# FindMeSAT_MB_1V1.net
KiCad netlist of a schematic drawn in EAGLE
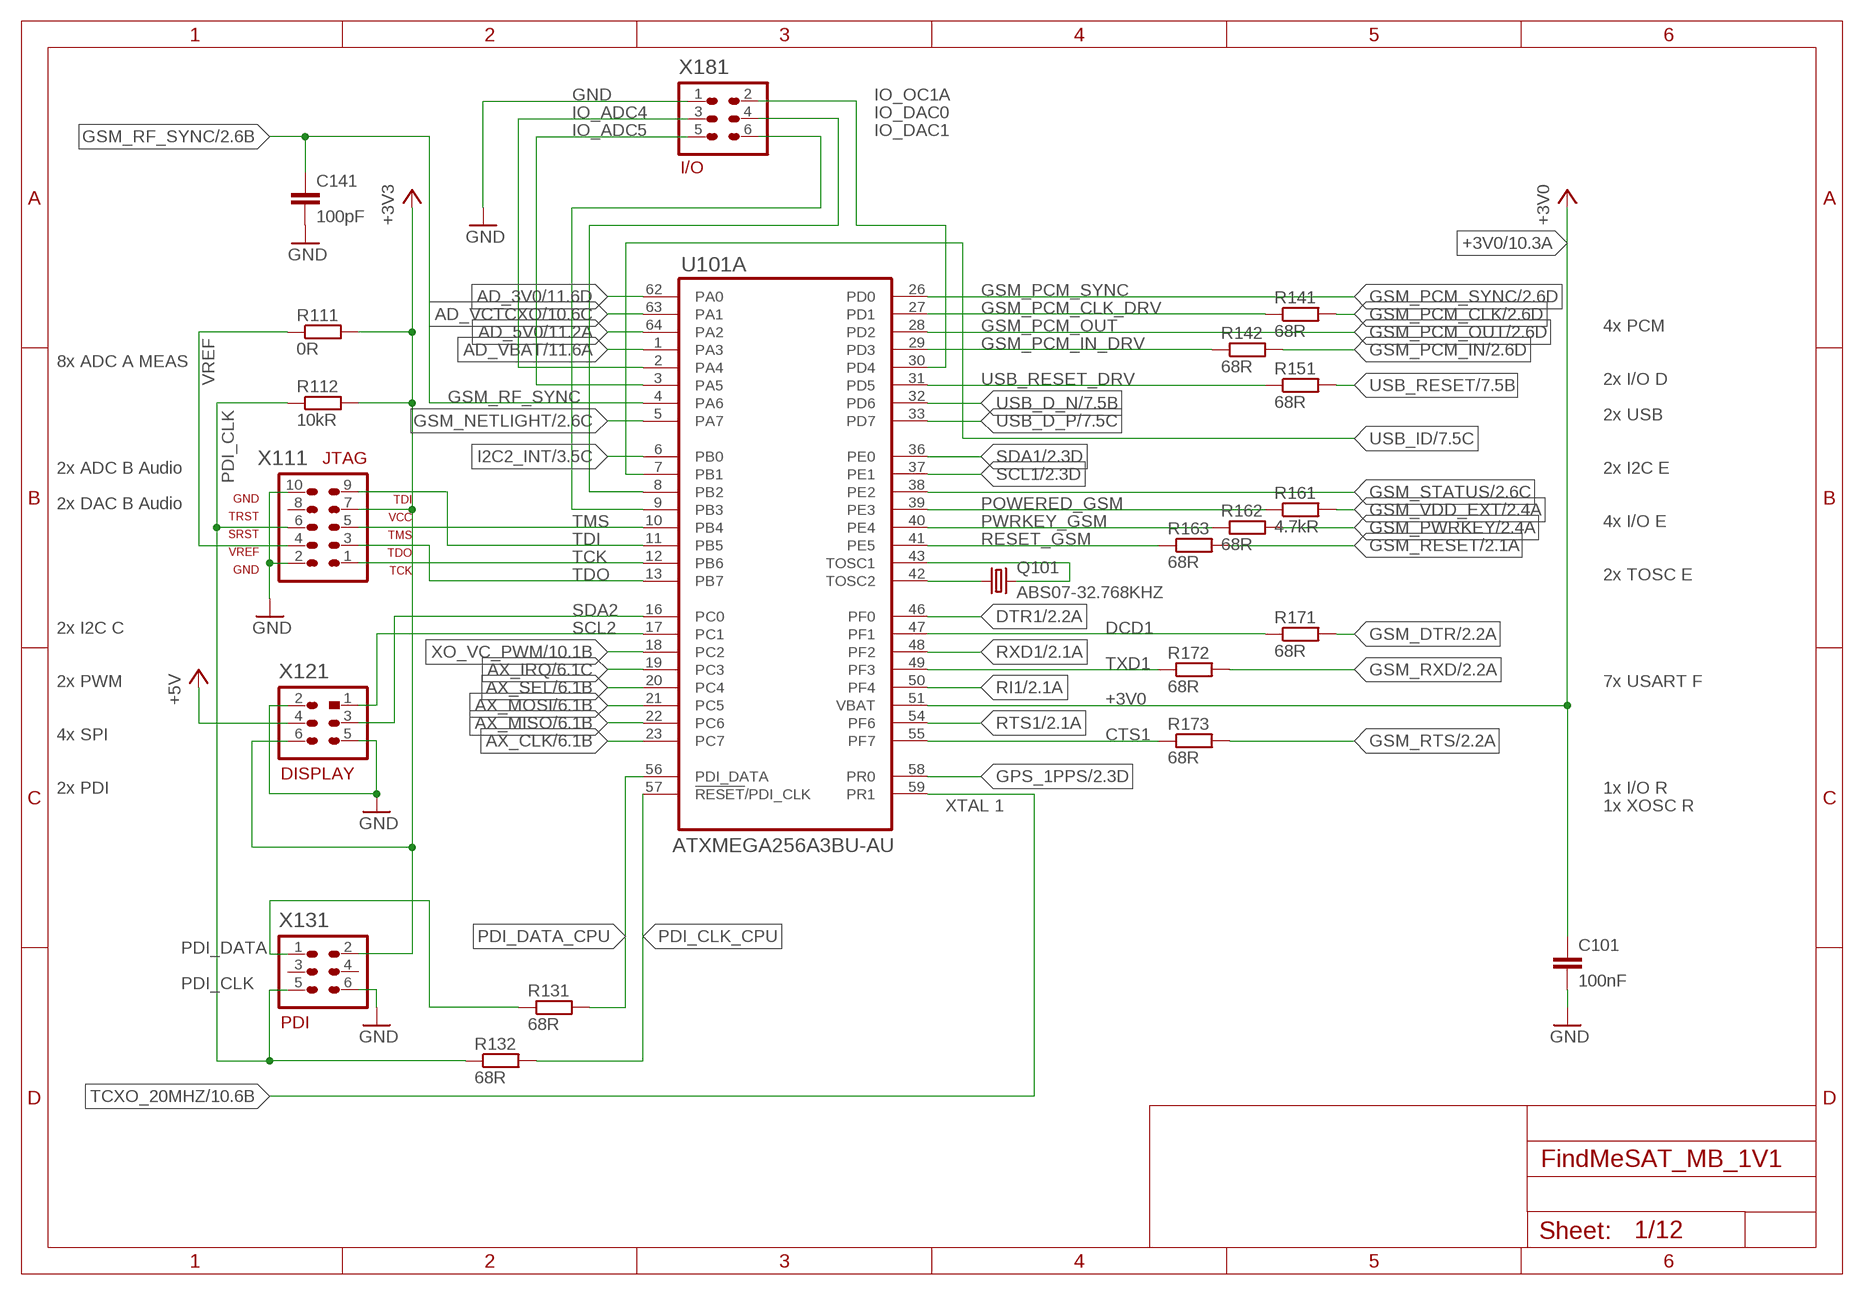
[diagram p0: schematic, sheet 1]
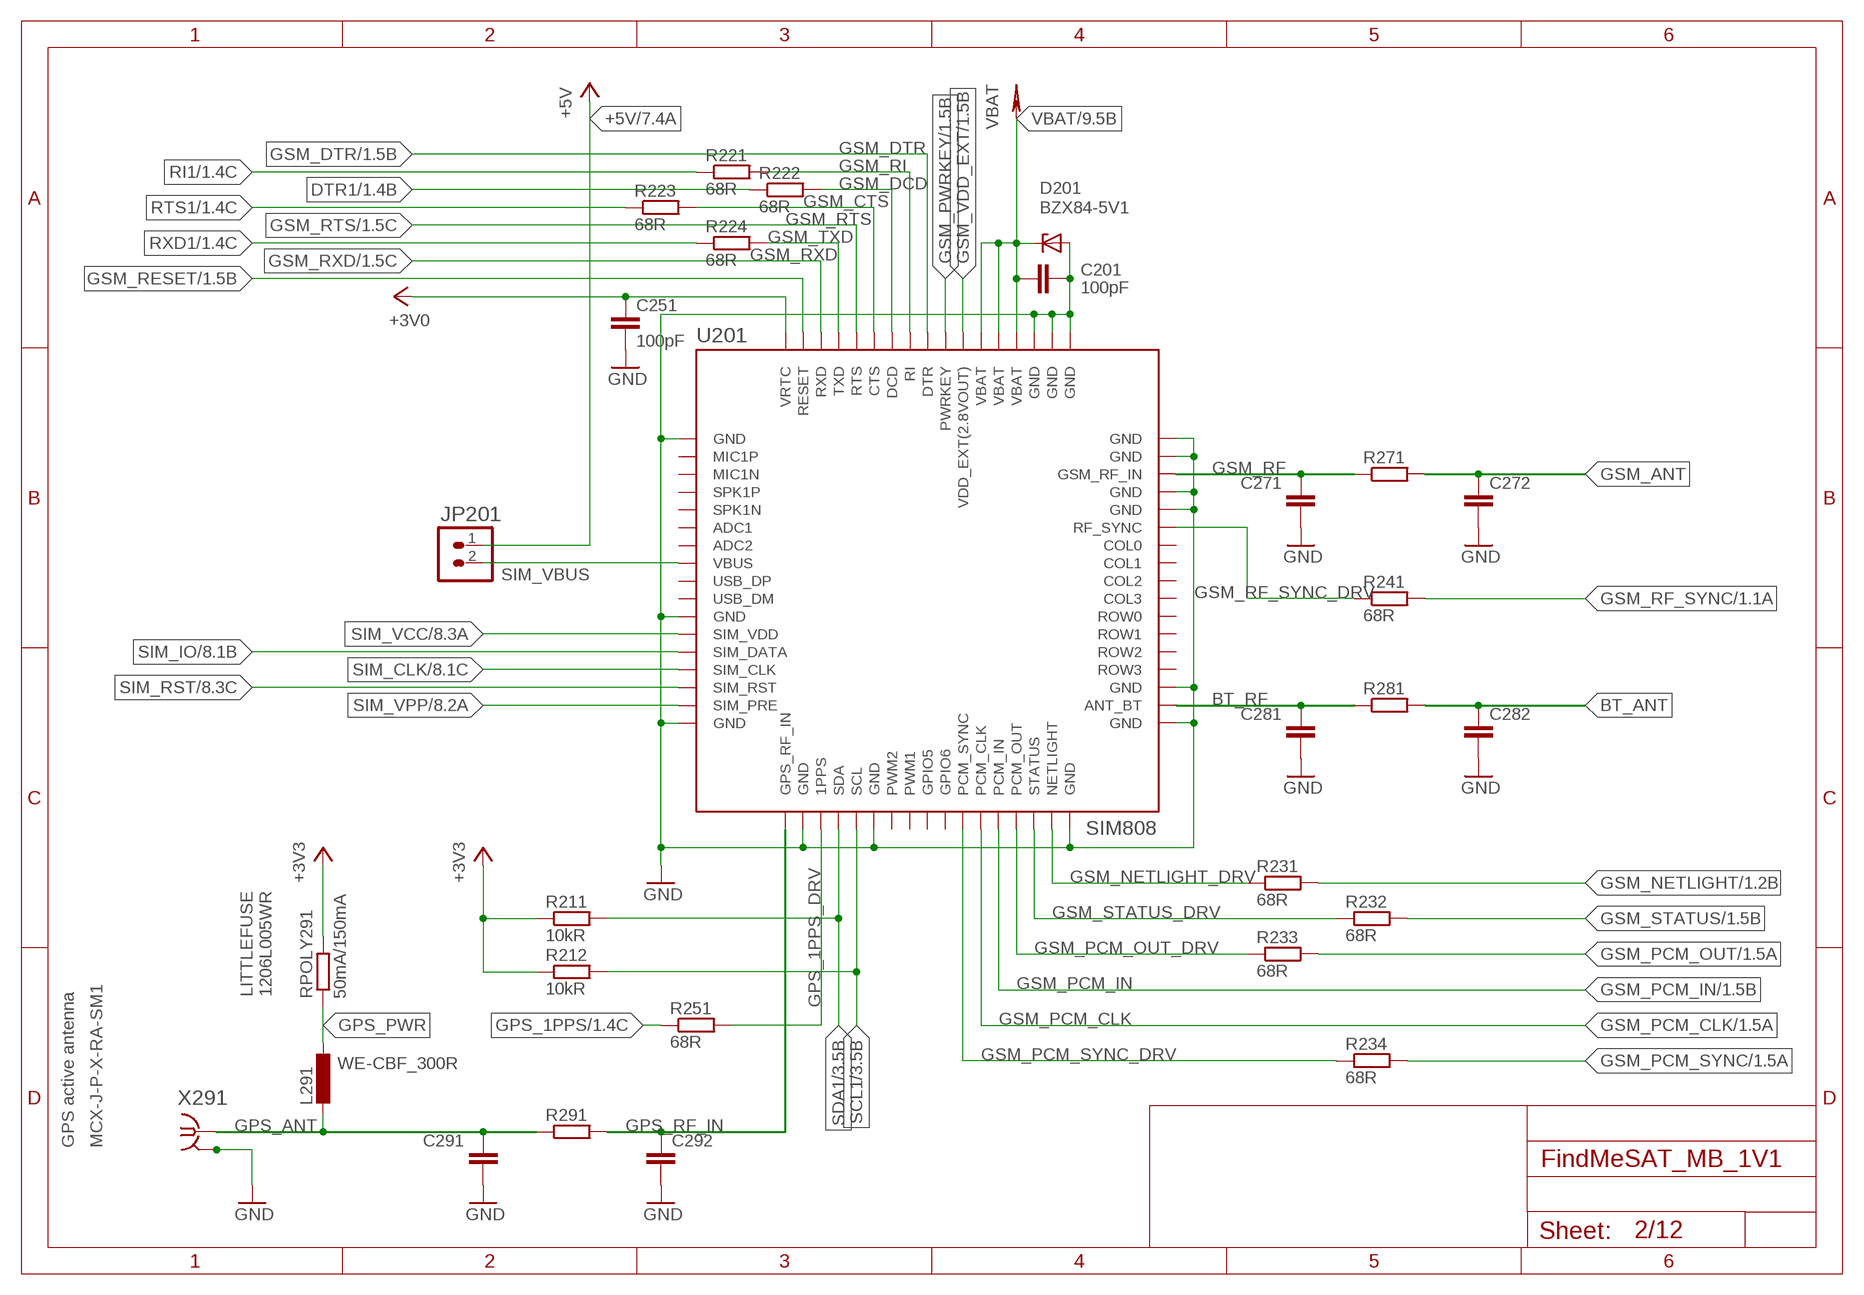
[diagram p1: schematic, sheet 2]
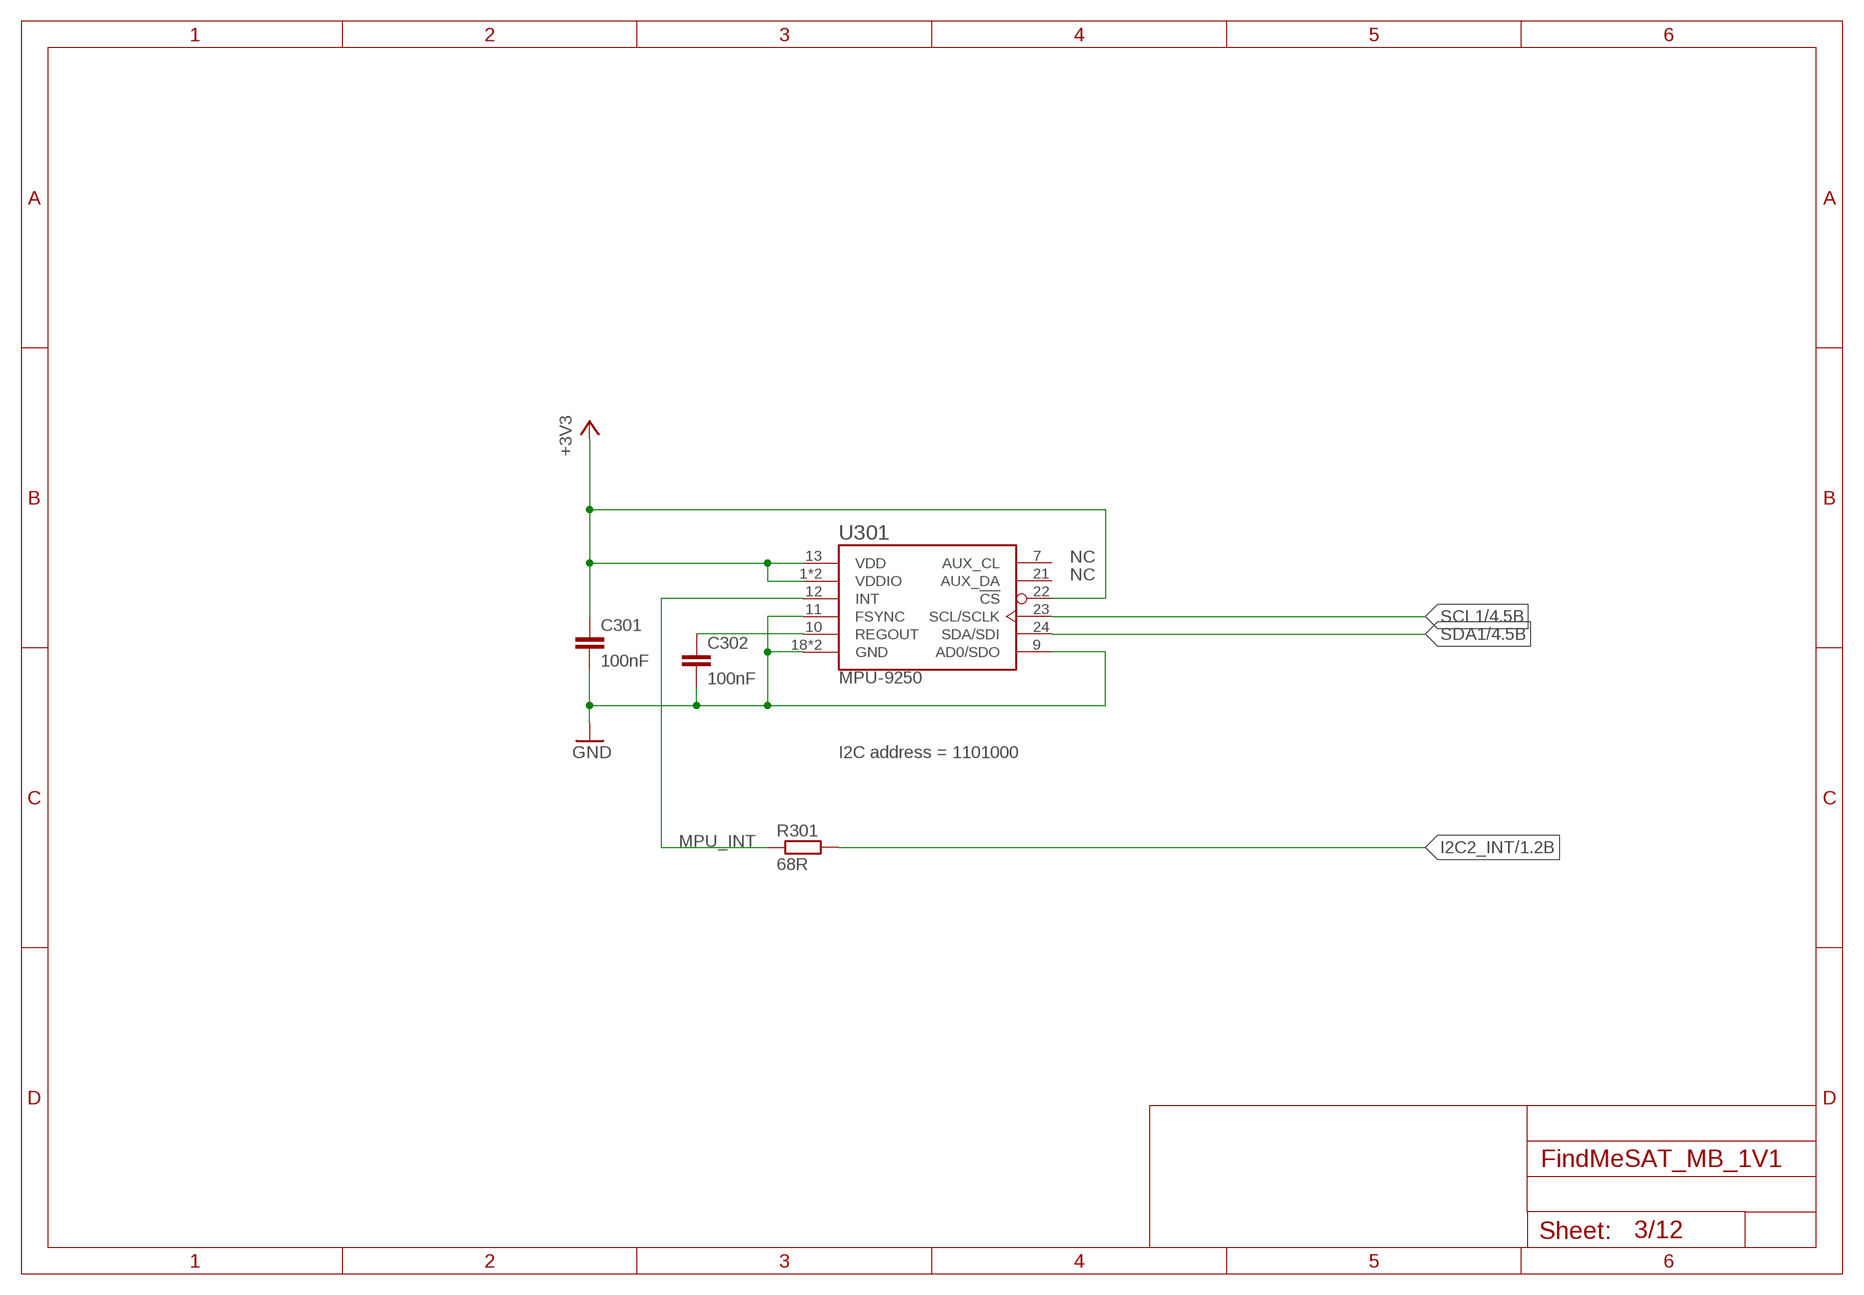
[diagram p2: schematic, sheet 3]
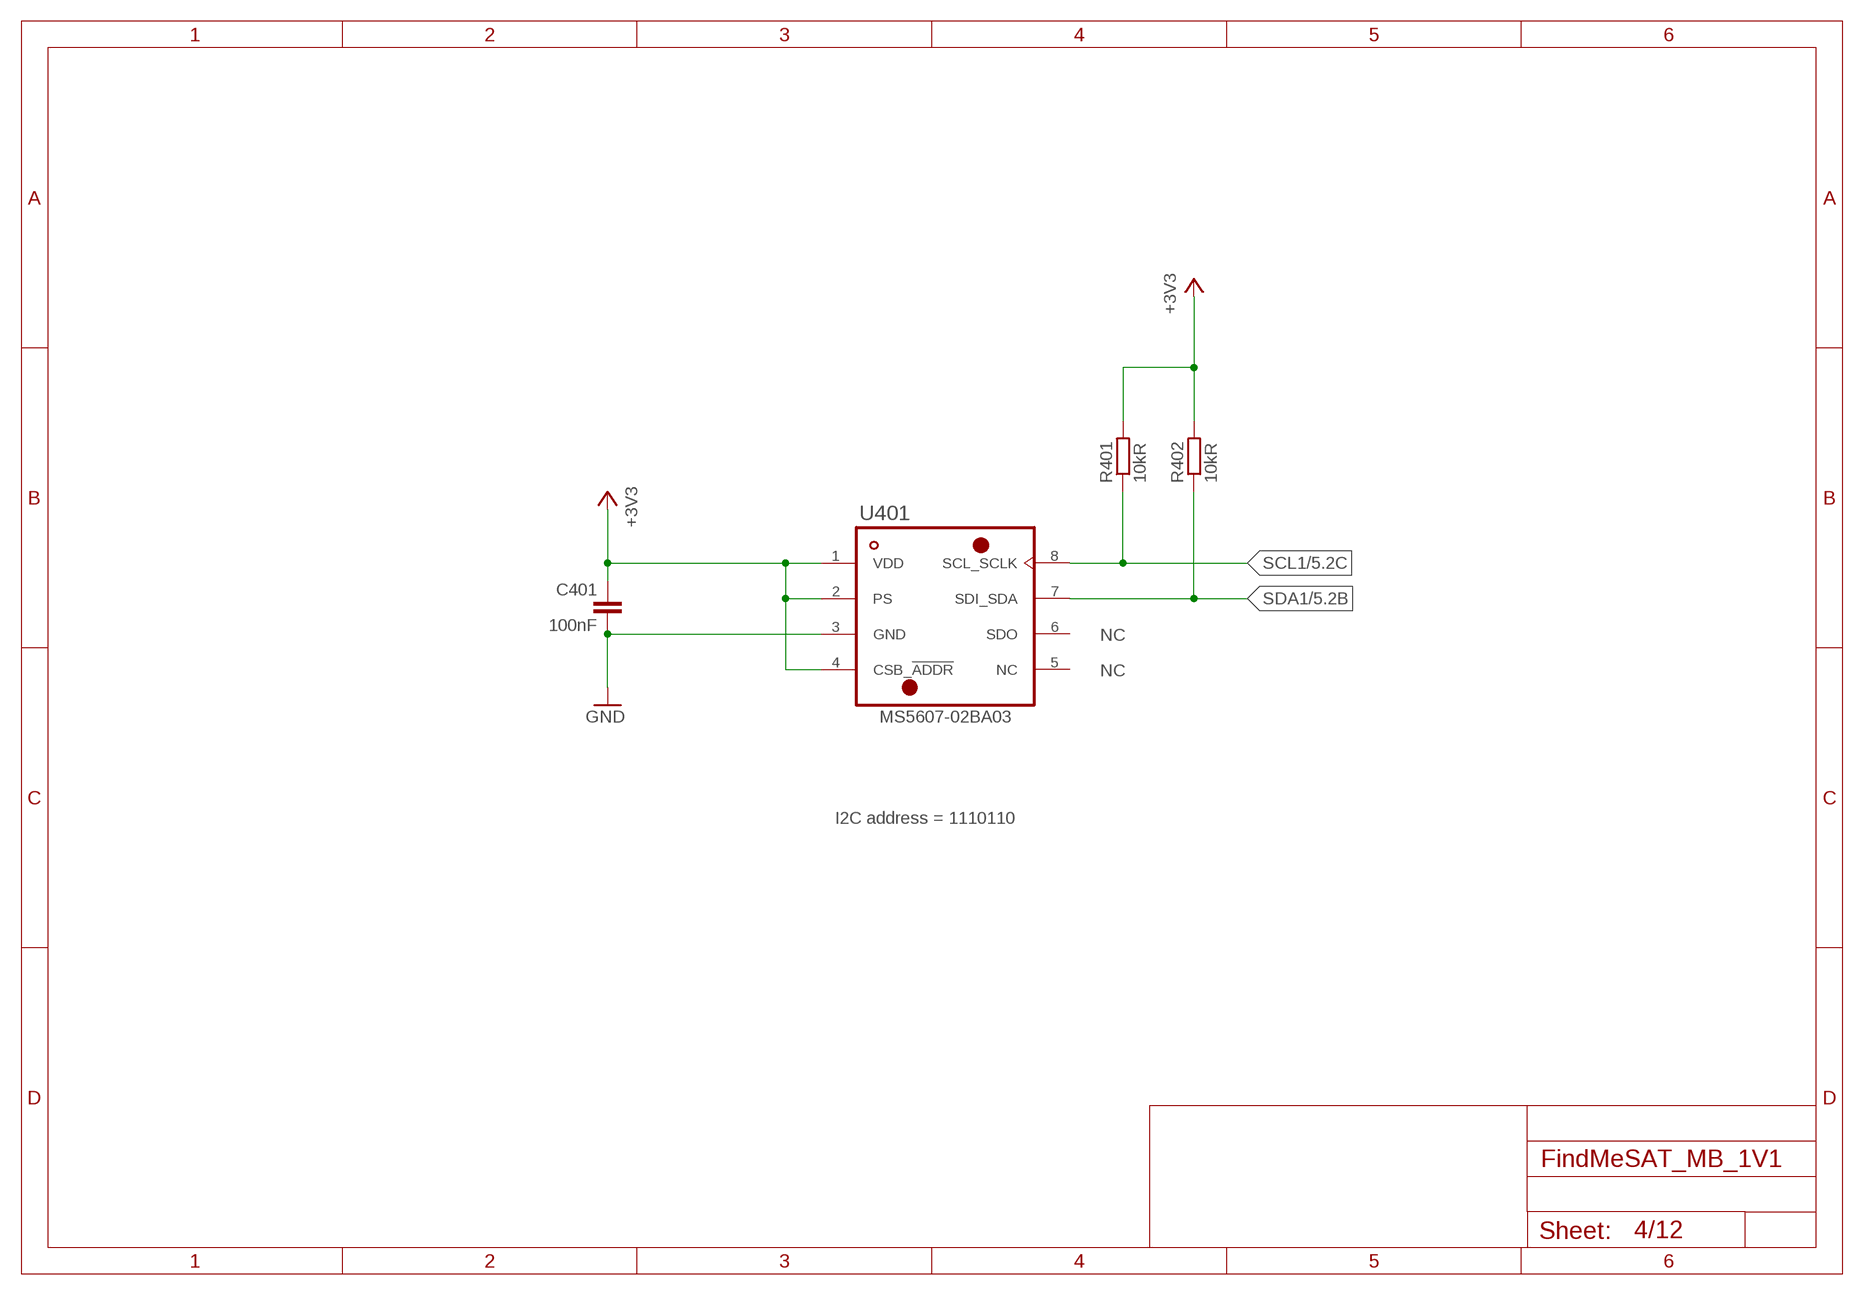
[diagram p3: schematic, sheet 4]
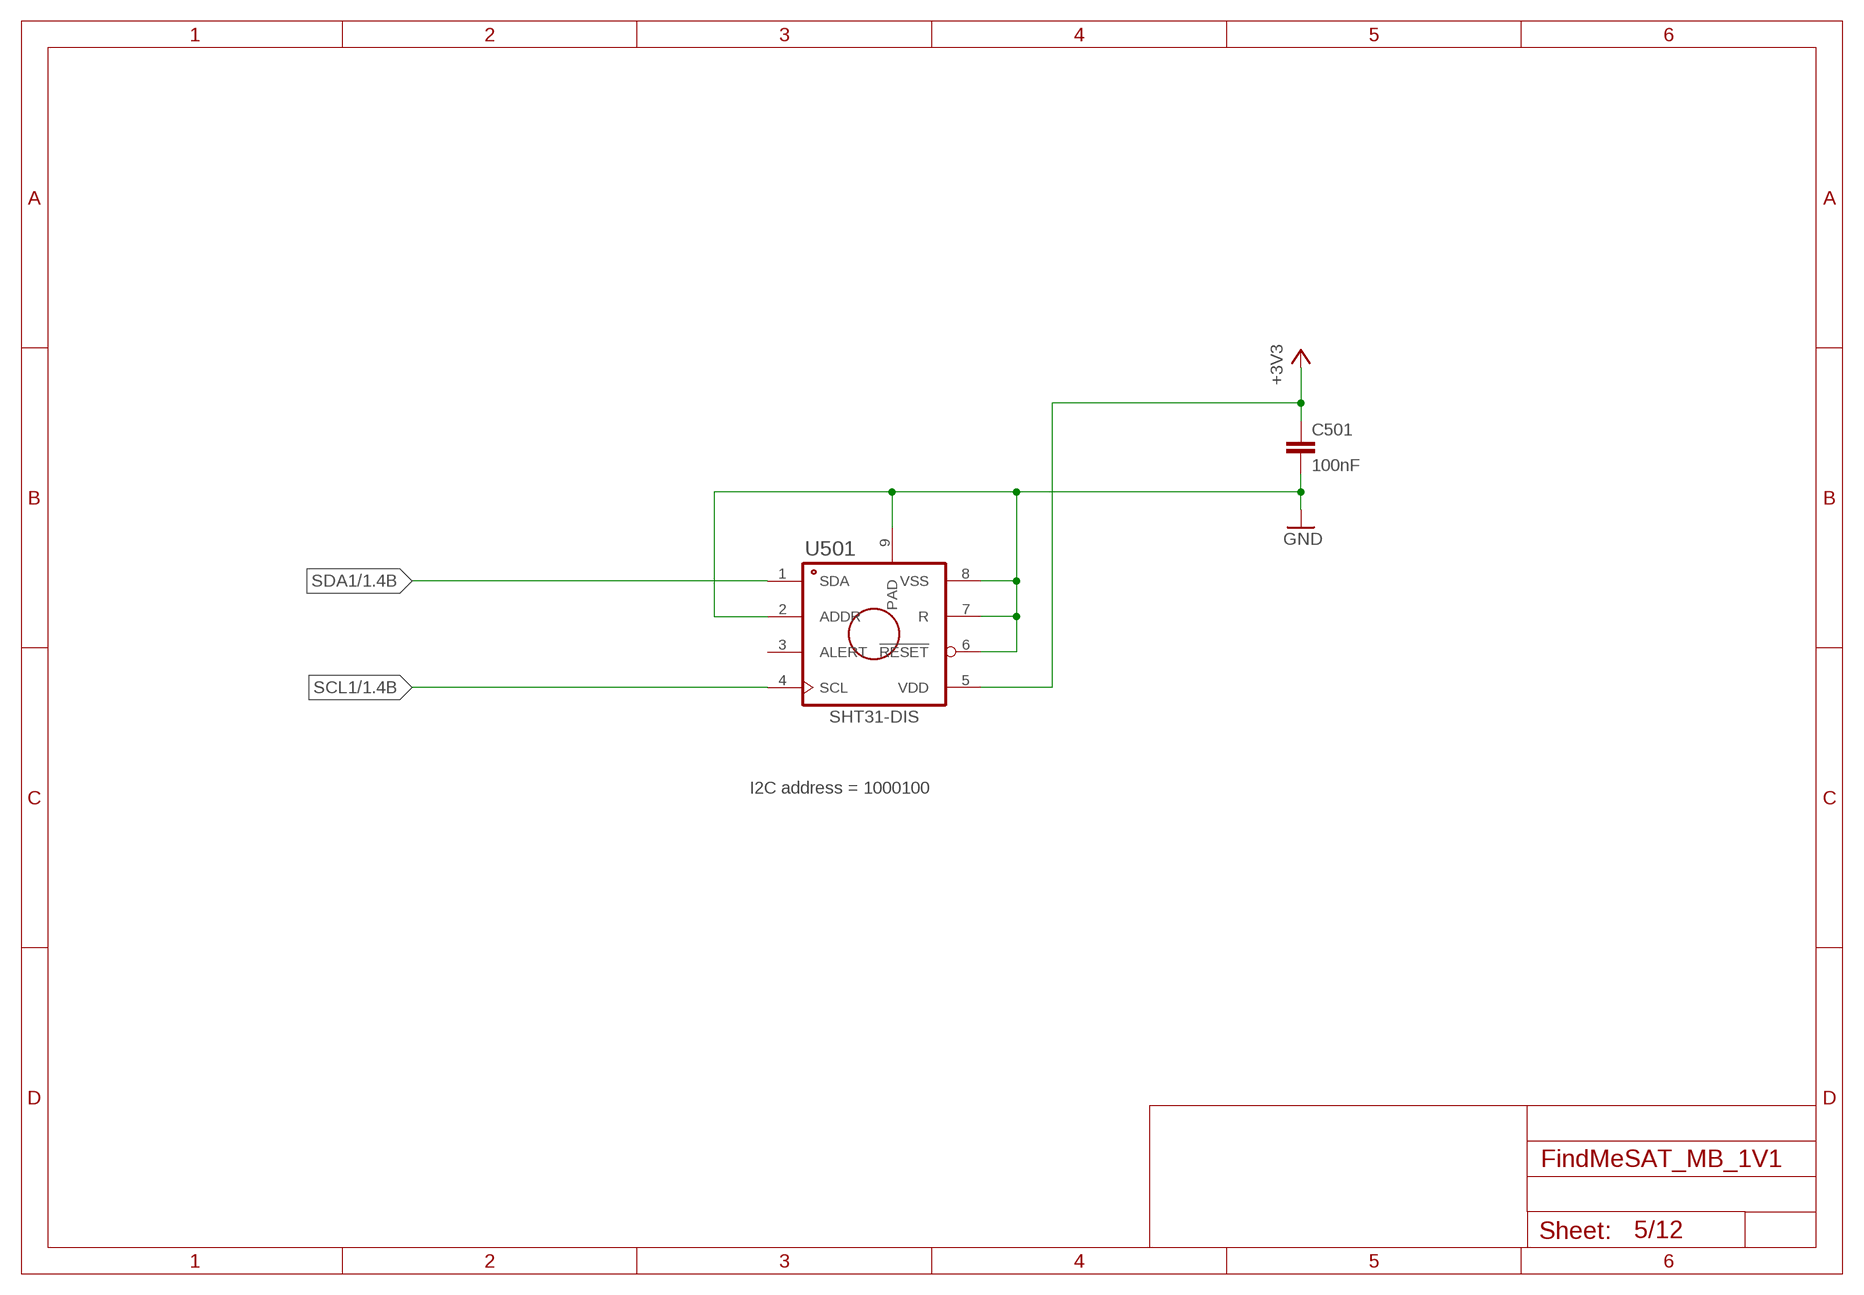
[diagram p4: schematic, sheet 5]
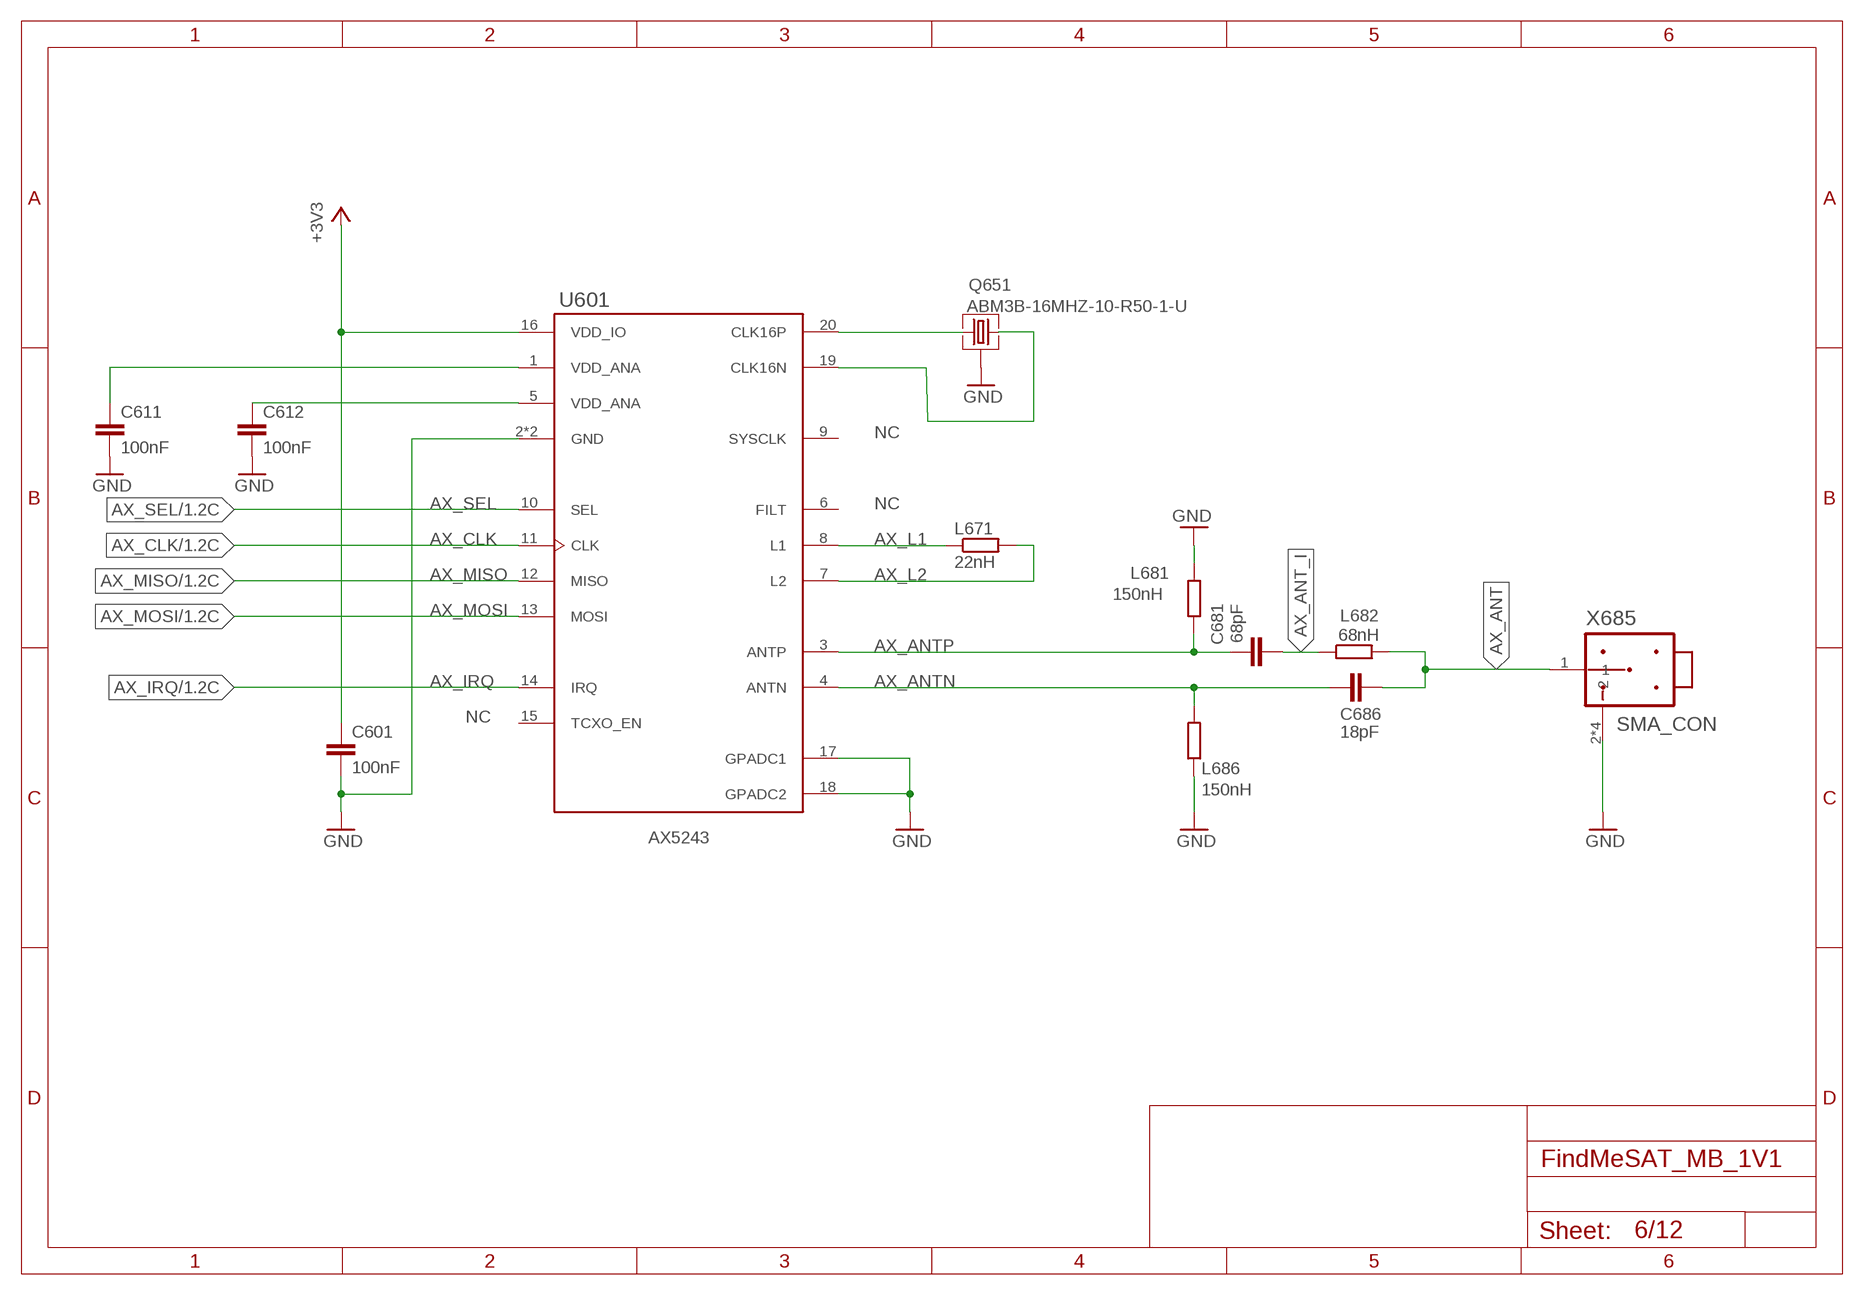
[diagram p5: schematic, sheet 6]
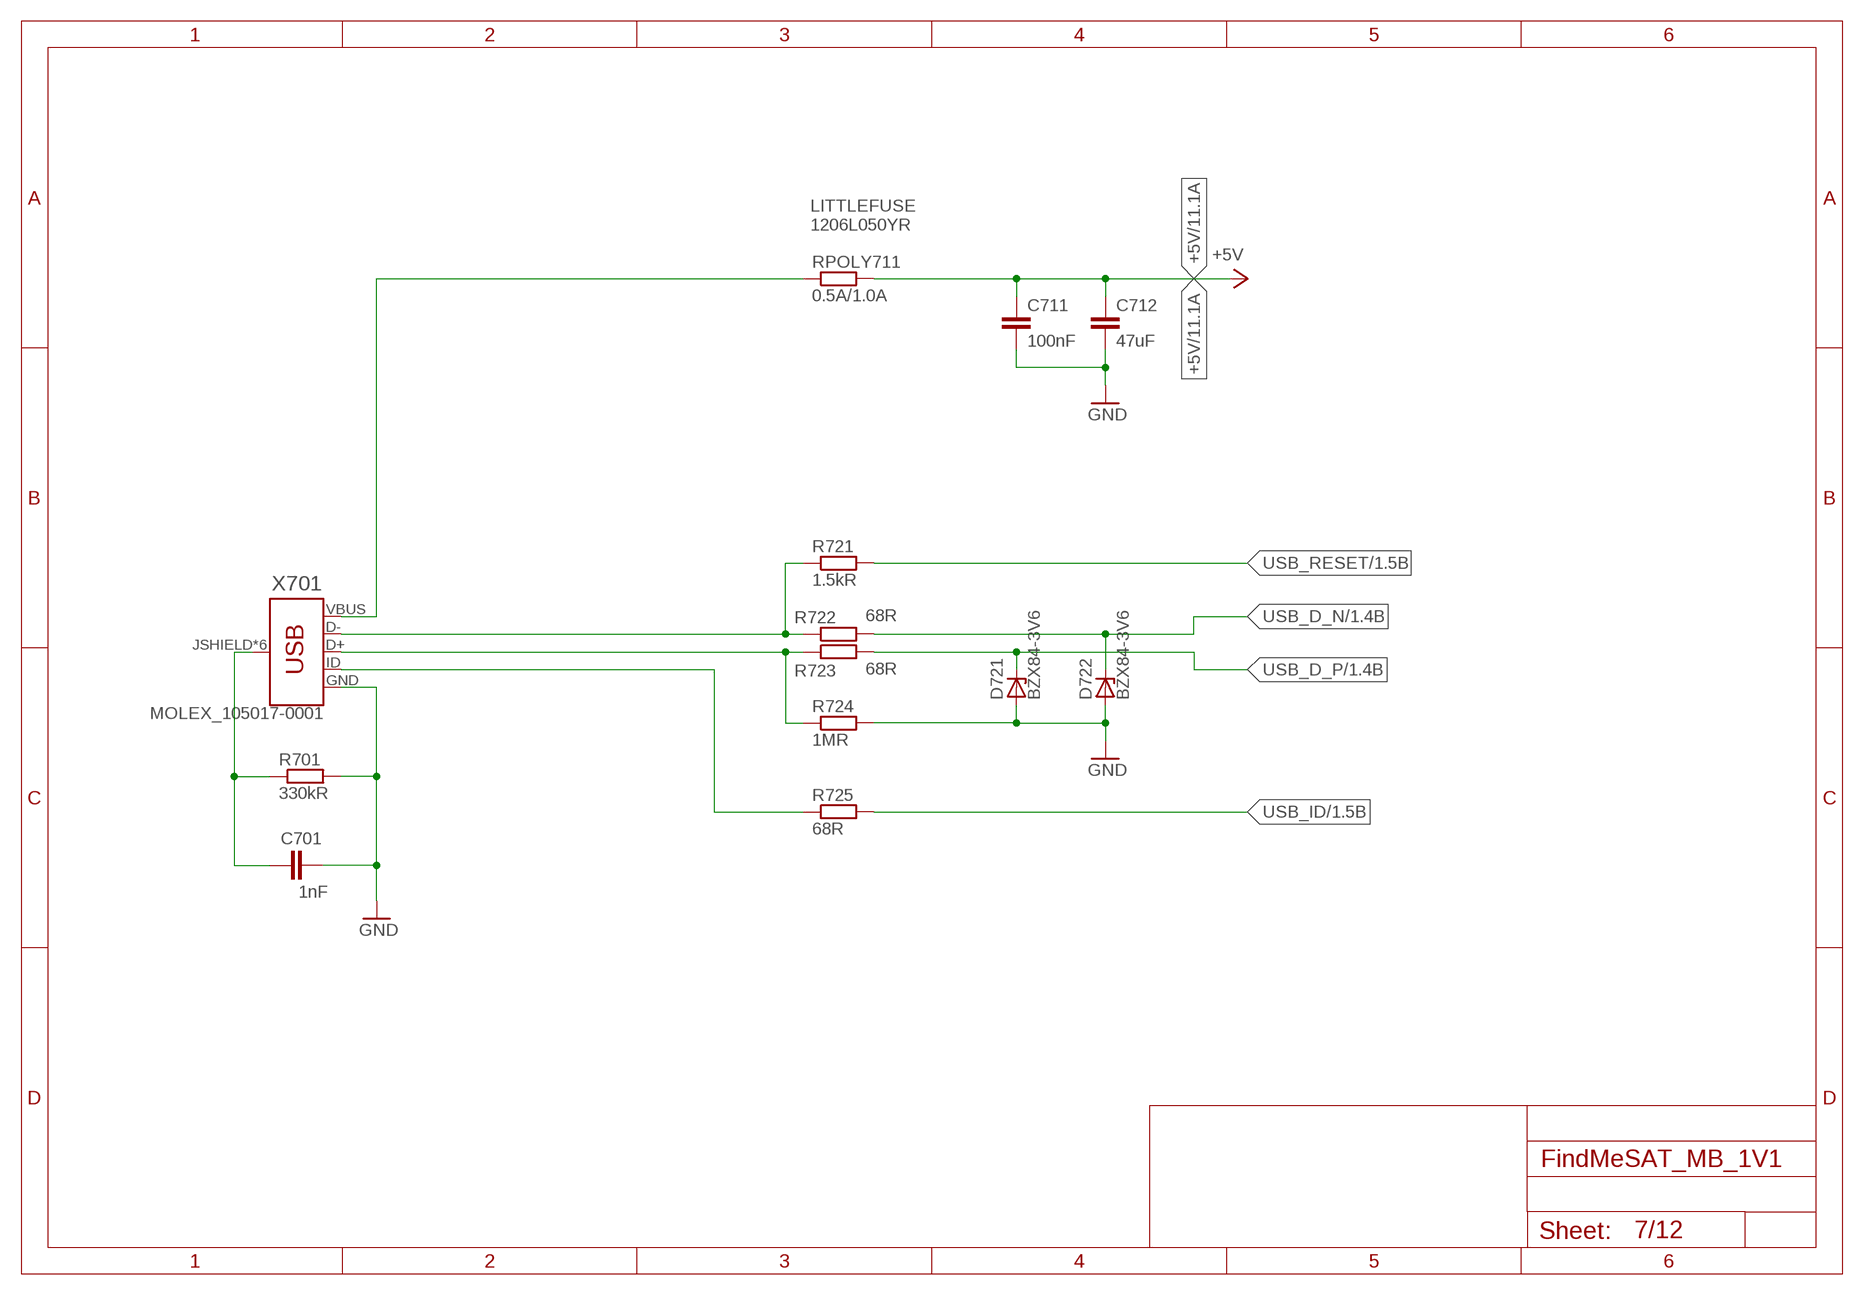
[diagram p6: schematic, sheet 7]
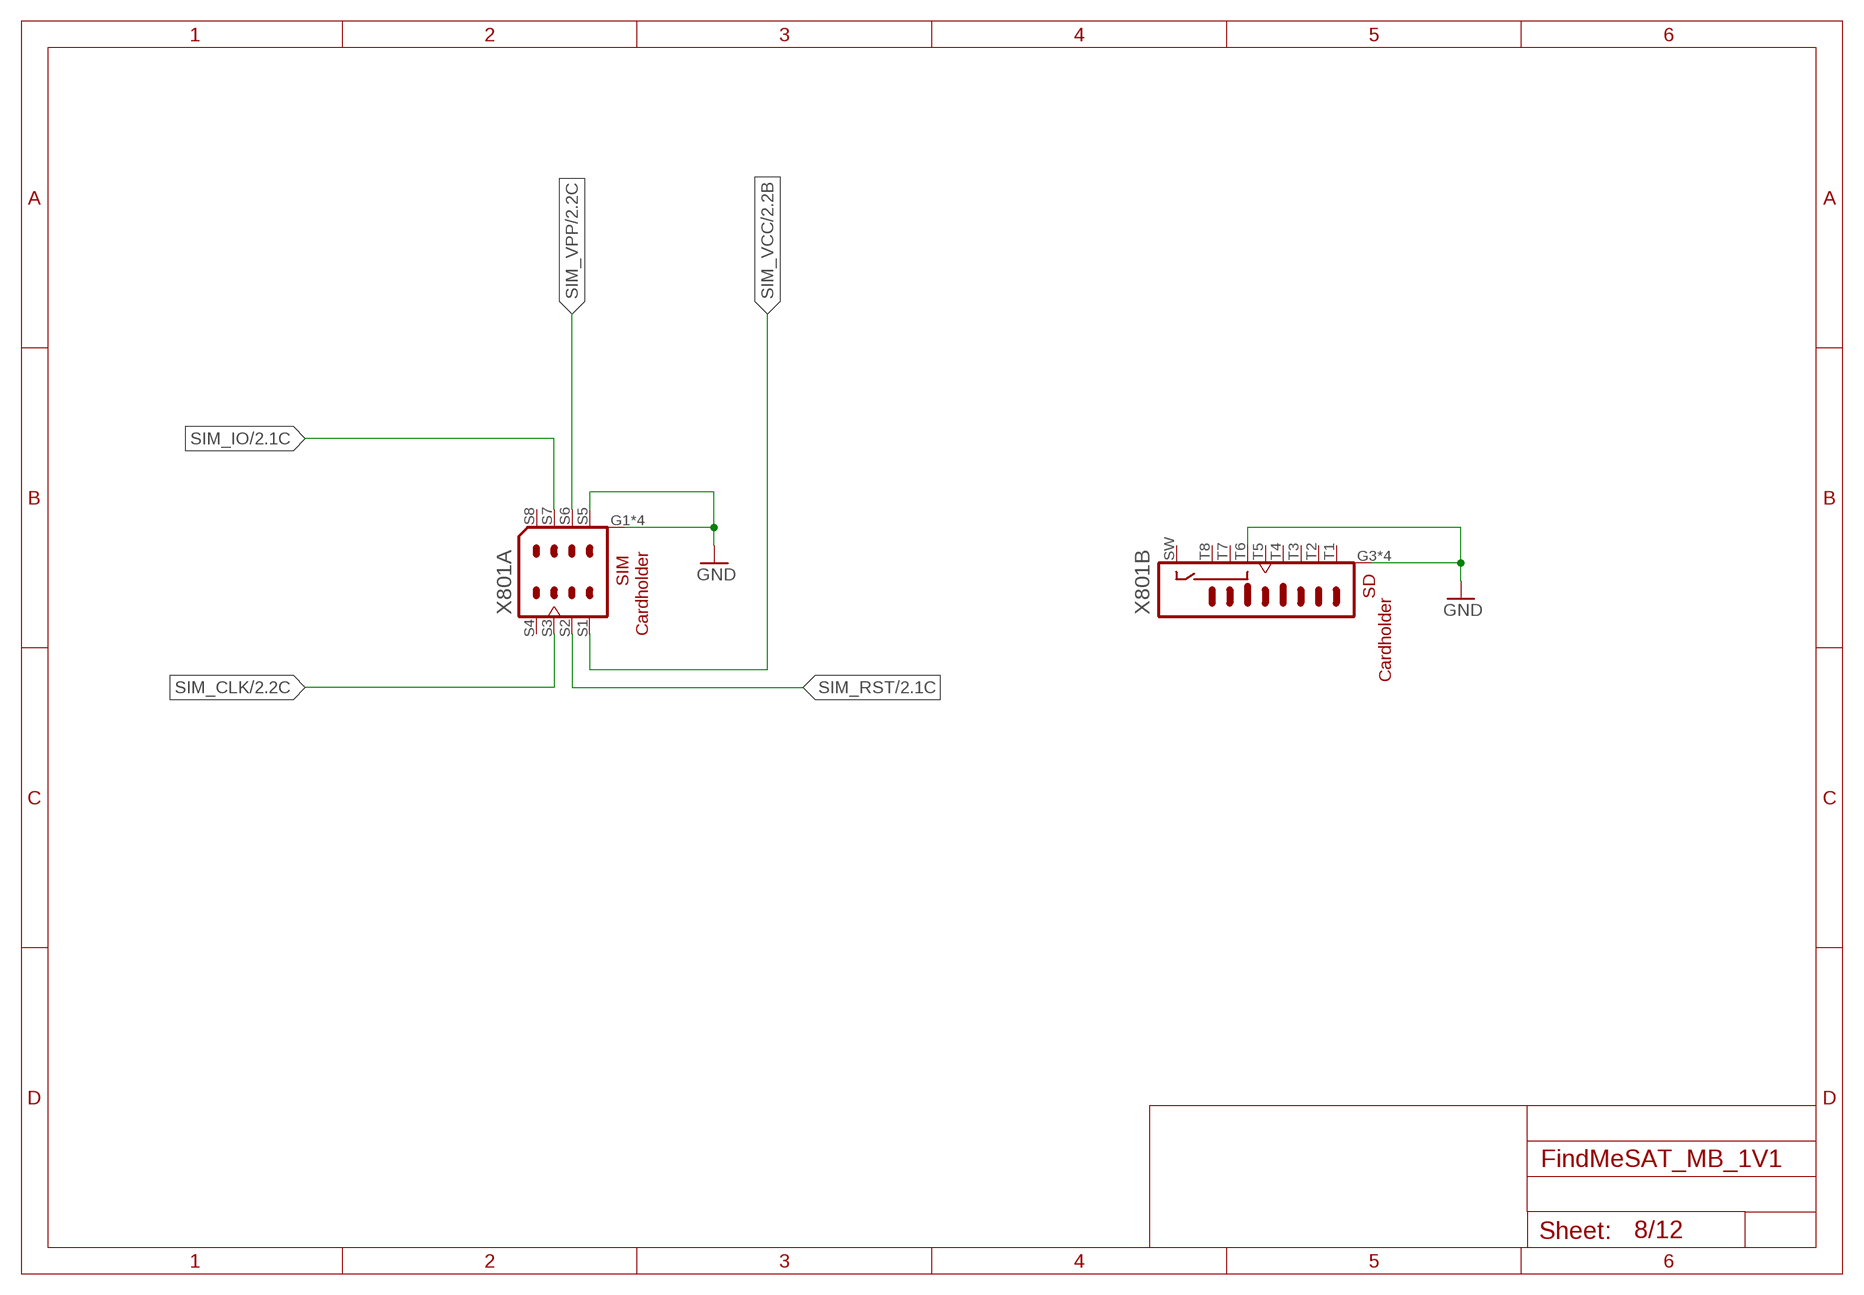
[diagram p7: schematic, sheet 8]
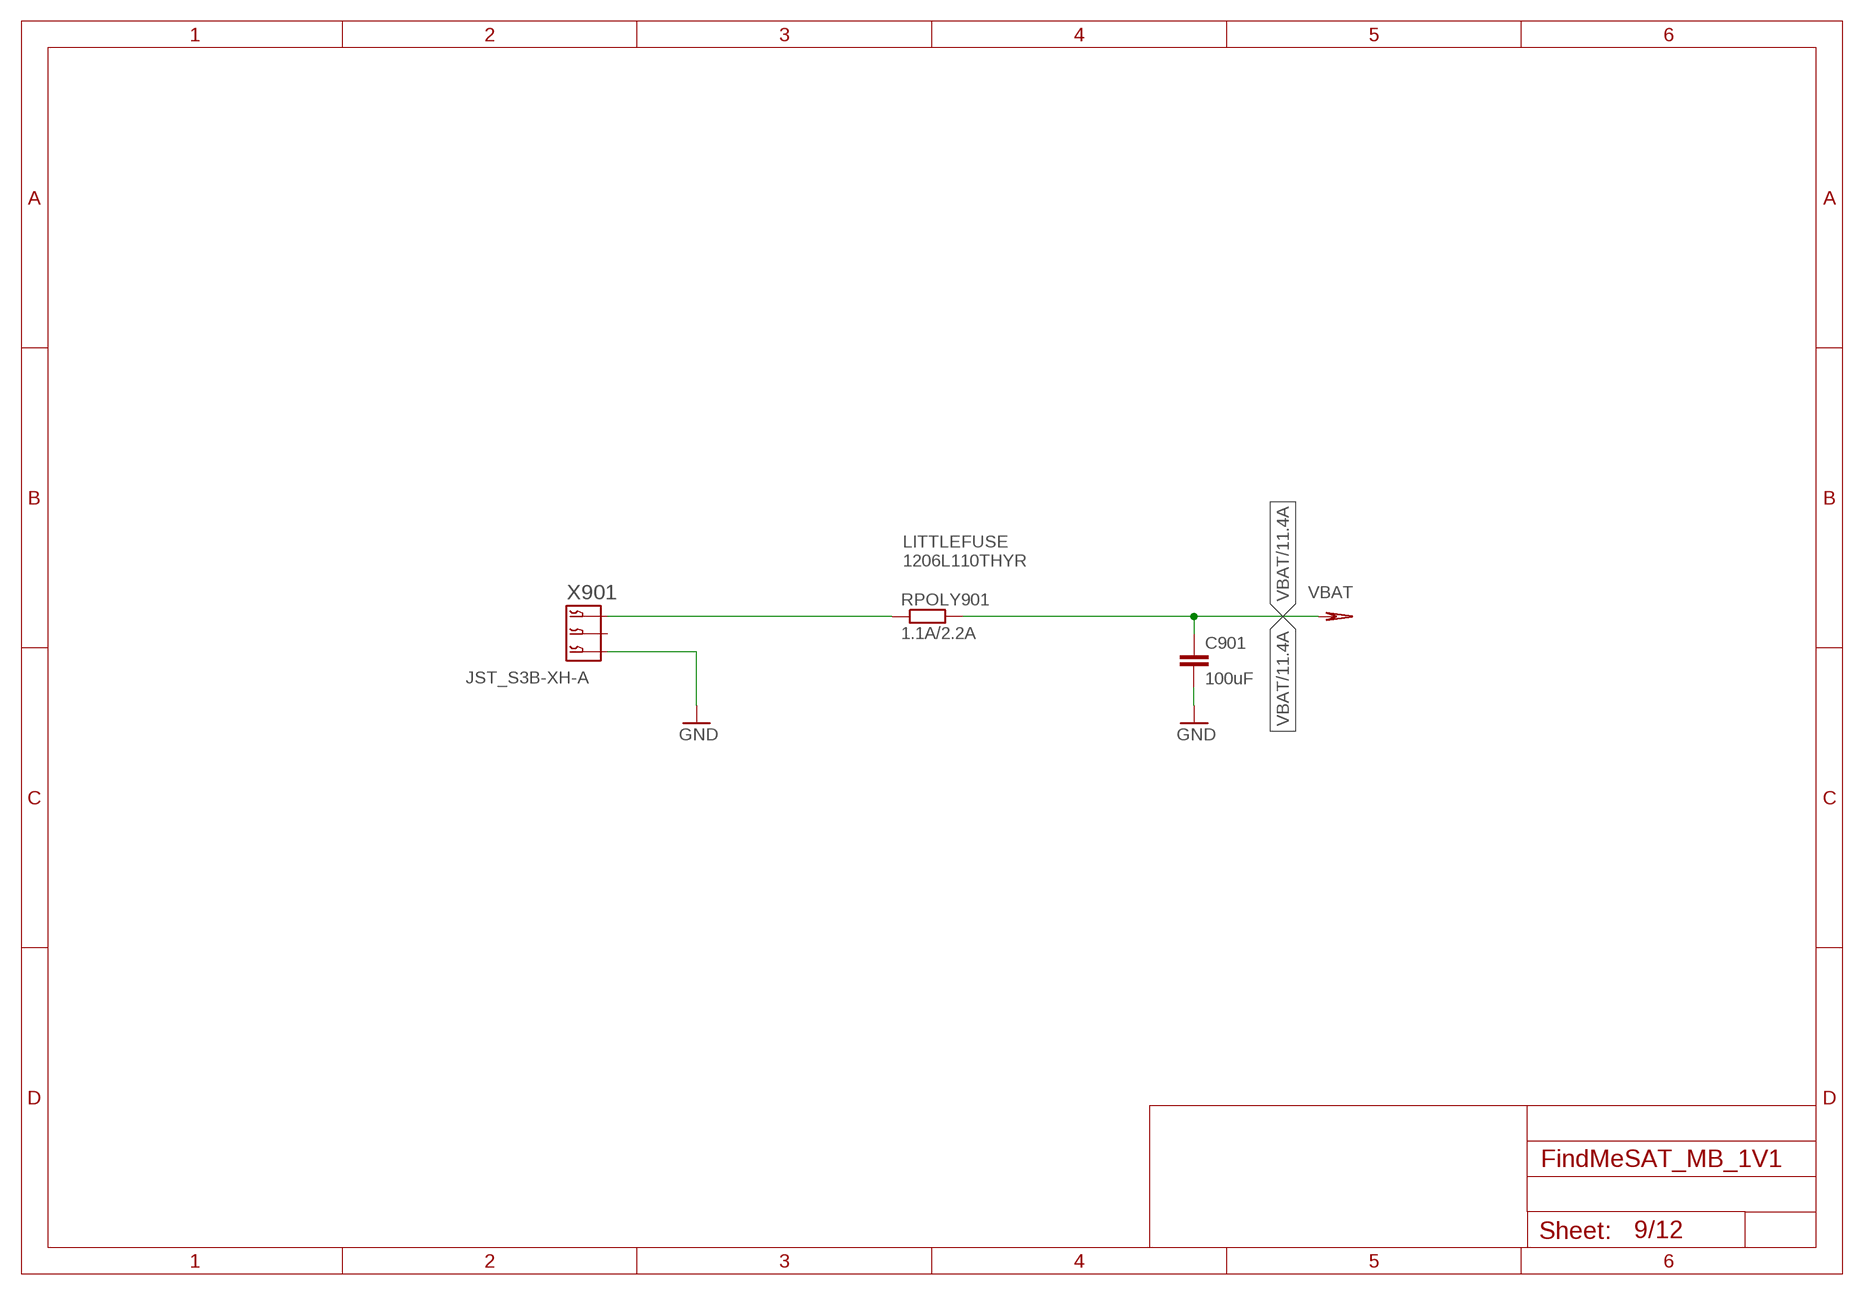
[diagram p8: schematic, sheet 9]
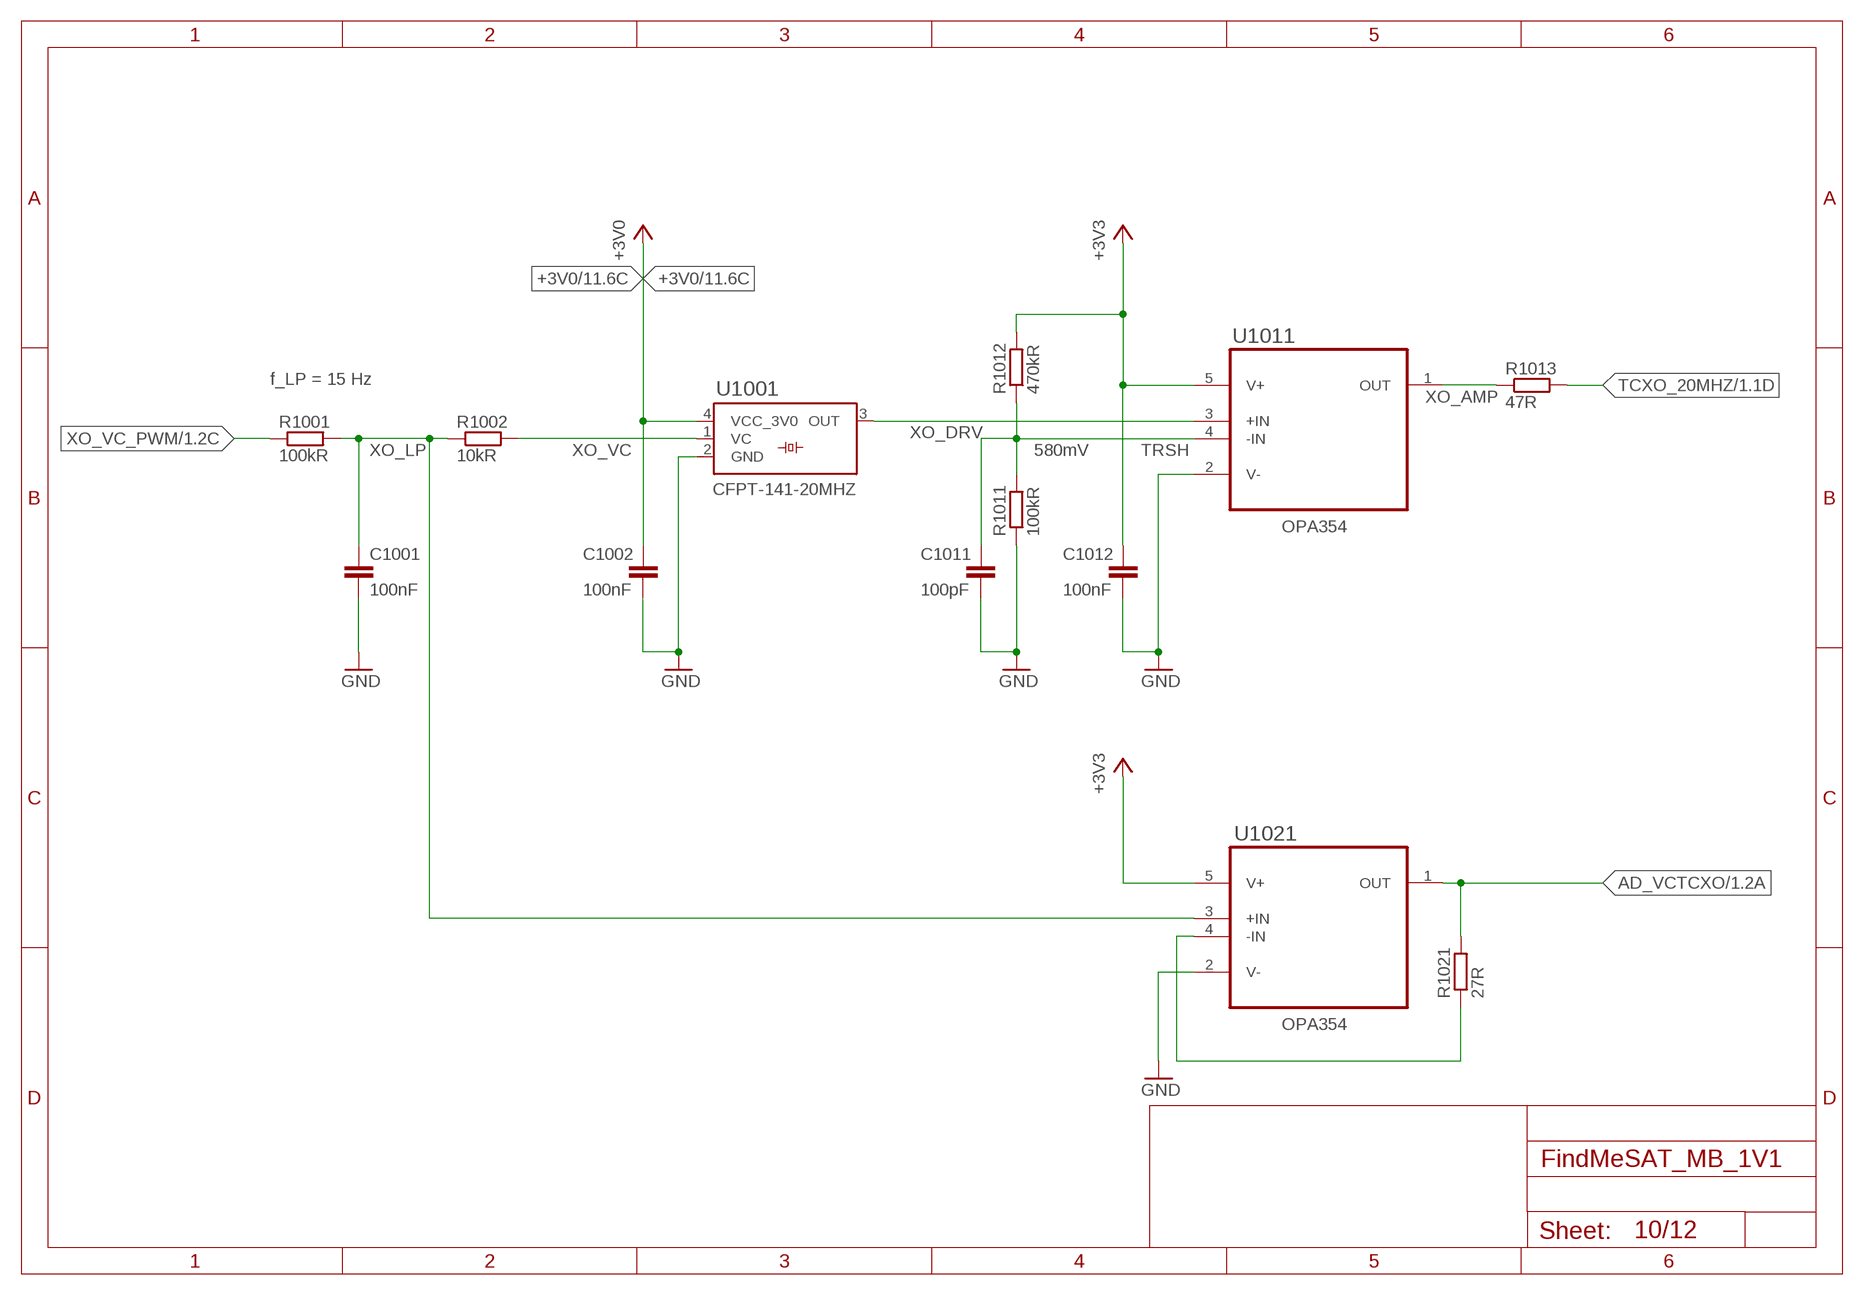
[diagram p9: schematic, sheet 10]
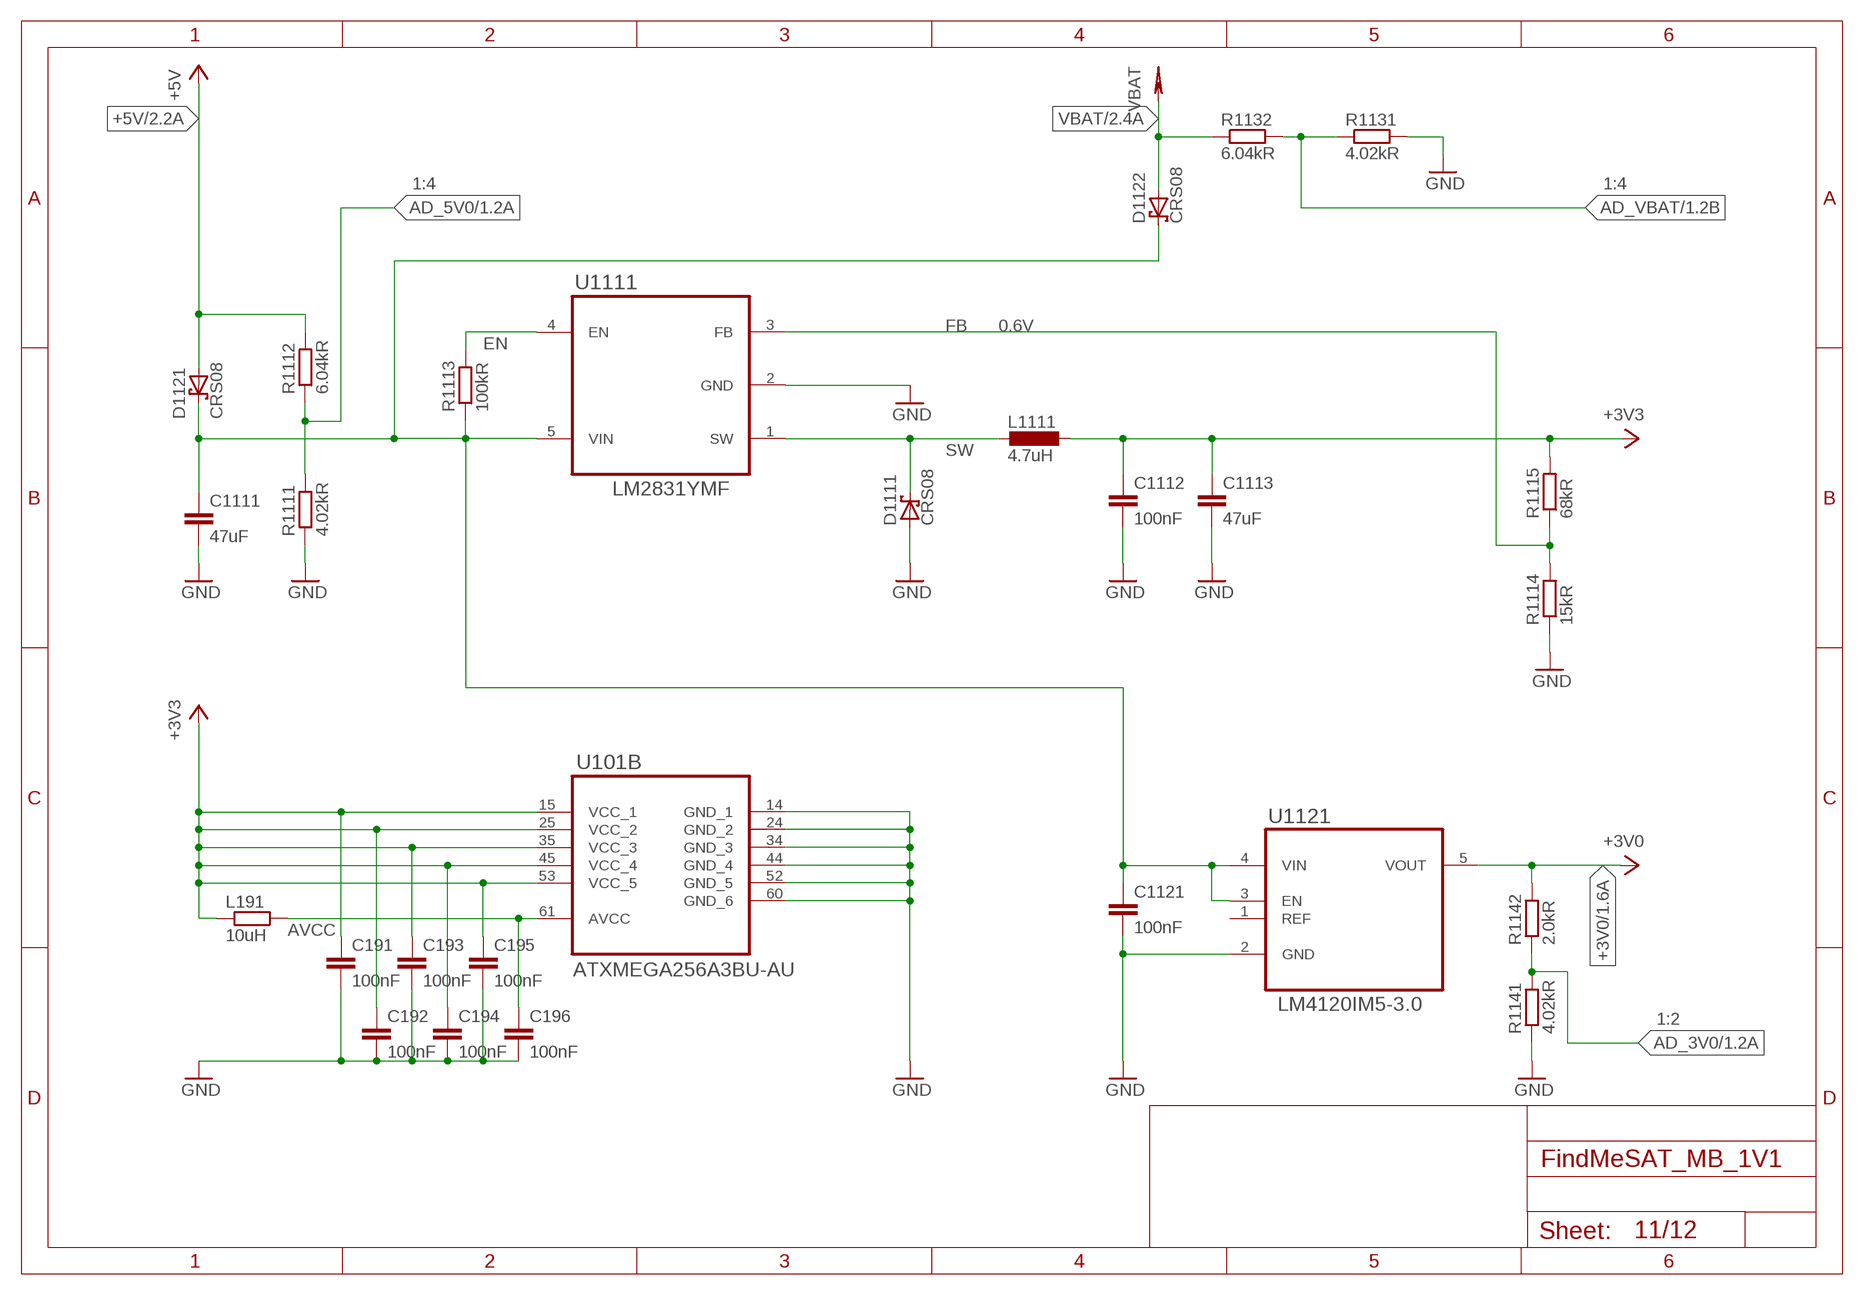
[diagram p10: schematic, sheet 11]
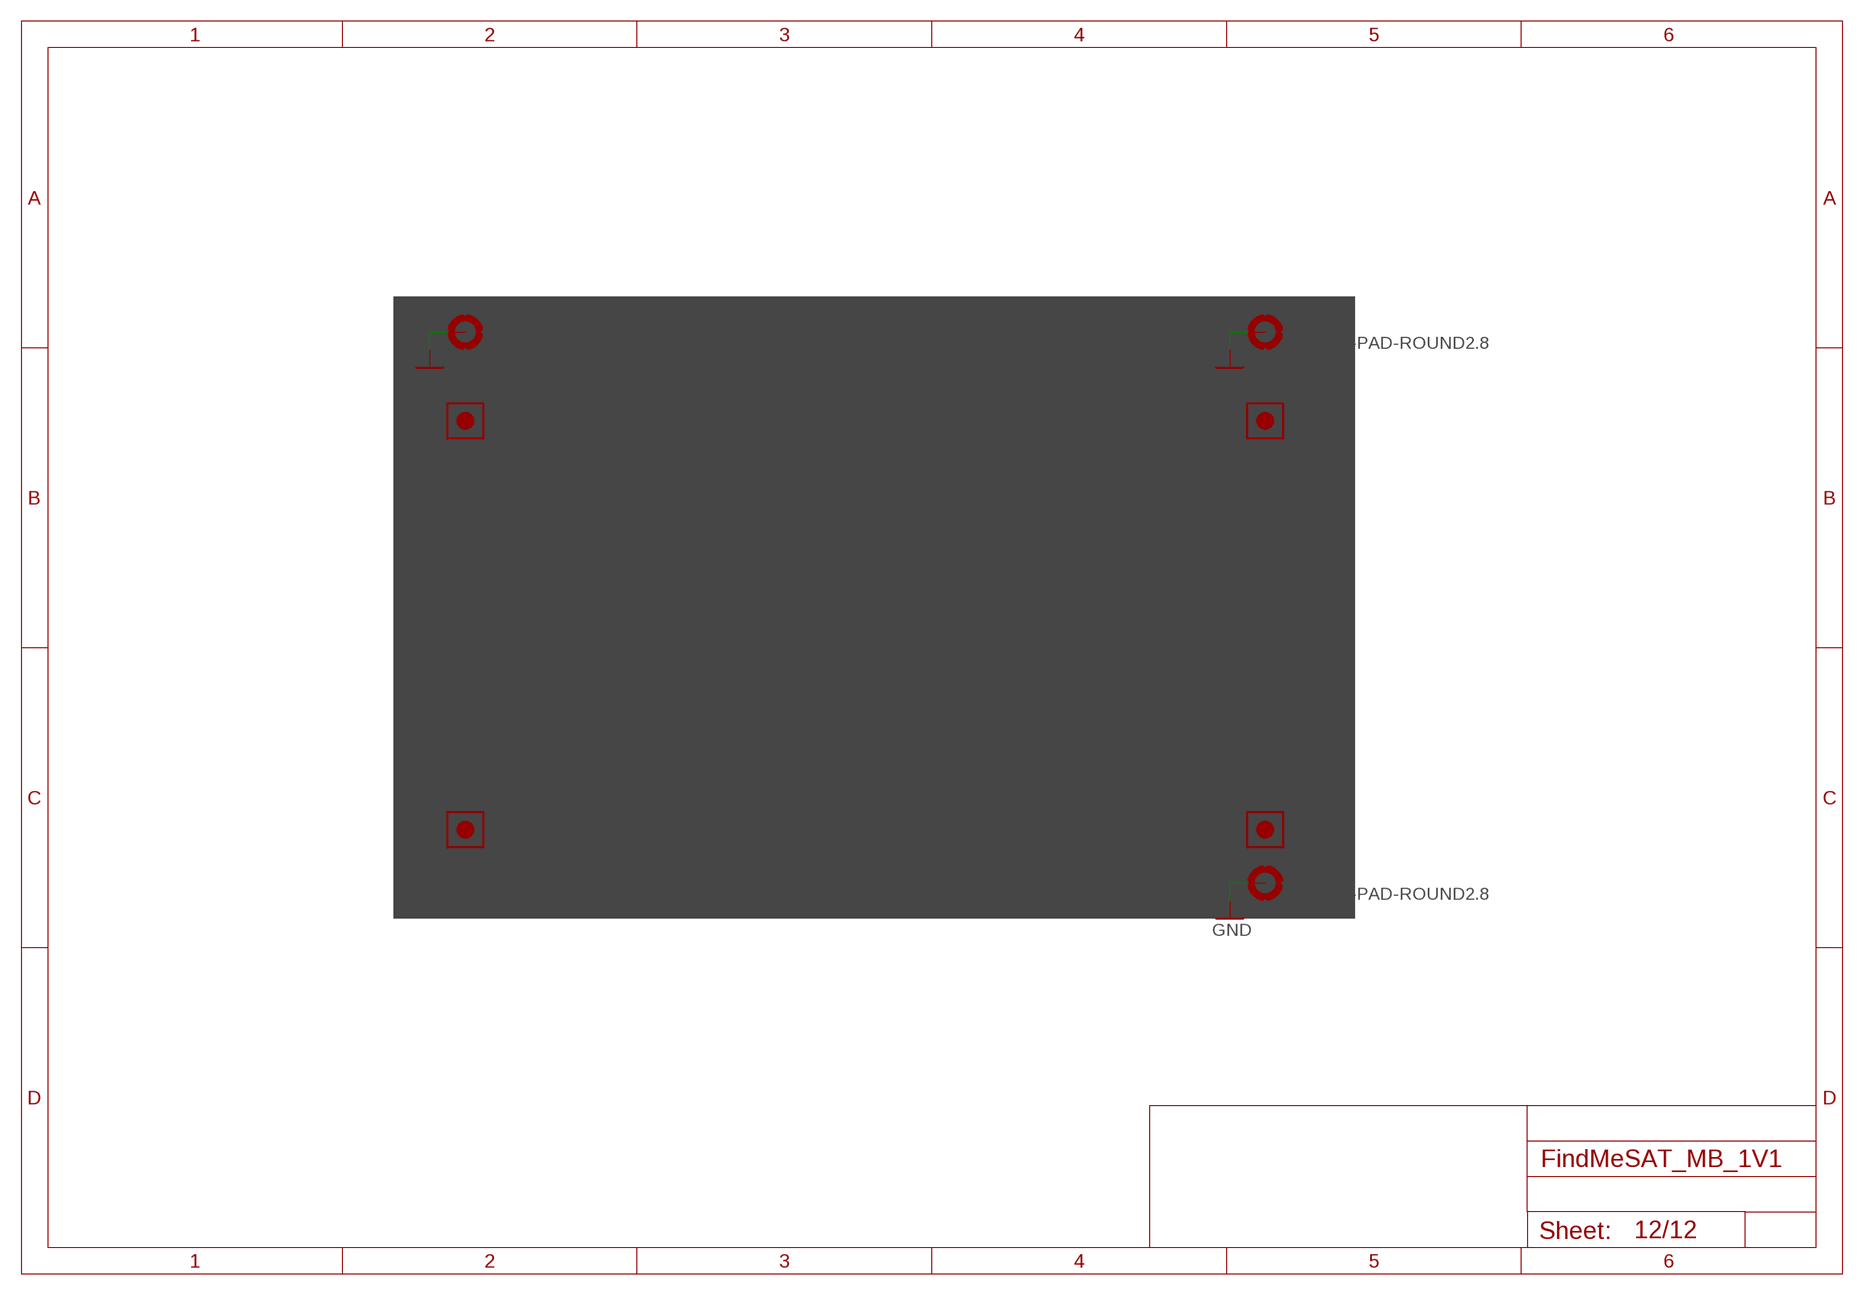
[diagram p11: schematic, sheet 12]

(export (version "E")
  (design (tool "Eeschema 10.0.6"))
  (components
    (comp (ref "C301")
      (value "100nF")
      (footprint "eagle-import:C0603")
      (libsource (lib "eagle-import") (part "C-EUC0603"))
    )
    (comp (ref "C302")
      (value "100nF")
      (footprint "eagle-import:C0603")
      (libsource (lib "eagle-import") (part "C-EUC0603"))
    )
    (comp (ref "R301")
      (value "68R")
      (footprint "eagle-import:R0603")
      (libsource (lib "eagle-import") (part "R-EU_R0603"))
    )
    (comp (ref "U301")
      (value "MPU-9250")
      (footprint "eagle-import:QFN24-3X3")
      (libsource (lib "eagle-import") (part "MPU-9250"))
    )
    (comp (ref "C191")
      (value "100nF")
      (footprint "eagle-import:C0603")
      (libsource (lib "eagle-import") (part "C-EUC0603"))
    )
    (comp (ref "C192")
      (value "100nF")
      (footprint "eagle-import:C0603")
      (libsource (lib "eagle-import") (part "C-EUC0603"))
    )
    (comp (ref "C193")
      (value "100nF")
      (footprint "eagle-import:C0603")
      (libsource (lib "eagle-import") (part "C-EUC0603"))
    )
    (comp (ref "C194")
      (value "100nF")
      (footprint "eagle-import:C0603")
      (libsource (lib "eagle-import") (part "C-EUC0603"))
    )
    (comp (ref "C195")
      (value "100nF")
      (footprint "eagle-import:C0603")
      (libsource (lib "eagle-import") (part "C-EUC0603"))
    )
    (comp (ref "C196")
      (value "100nF")
      (footprint "eagle-import:C0603")
      (libsource (lib "eagle-import") (part "C-EUC0603"))
    )
    (comp (ref "C1111")
      (value "47uF")
      (footprint "eagle-import:C0805")
      (libsource (lib "eagle-import") (part "C-EUC0805"))
    )
    (comp (ref "C1112")
      (value "100nF")
      (footprint "eagle-import:C0603")
      (libsource (lib "eagle-import") (part "C-EUC0603"))
    )
    (comp (ref "C1113")
      (value "47uF")
      (footprint "eagle-import:C0805")
      (libsource (lib "eagle-import") (part "C-EUC0805"))
    )
    (comp (ref "C1121")
      (value "100nF")
      (footprint "eagle-import:C0603")
      (libsource (lib "eagle-import") (part "C-EUC0603"))
    )
    (comp (ref "D1111")
      (value "CRS08")
      (footprint "eagle-import:SOD80C")
      (libsource (lib "eagle-import") (part "CRS08"))
    )
    (comp (ref "D1121")
      (value "CRS08")
      (footprint "eagle-import:SOD80C")
      (libsource (lib "eagle-import") (part "CRS08"))
    )
    (comp (ref "D1122")
      (value "CRS08")
      (footprint "eagle-import:SOD80C")
      (libsource (lib "eagle-import") (part "CRS08"))
    )
    (comp (ref "L191")
      (value "10uH")
      (footprint "eagle-import:R0603")
      (libsource (lib "eagle-import") (part "R-EU_R0603"))
    )
    (comp (ref "L1111")
      (value "4.7uH")
      (footprint "eagle-import:L5650M")
      (libsource (lib "eagle-import") (part "L-EUL5650M"))
    )
    (comp (ref "R1111")
      (value "4.02kR")
      (footprint "eagle-import:R0603")
      (libsource (lib "eagle-import") (part "R-EU_R0603"))
    )
    (comp (ref "R1112")
      (value "6.04kR")
      (footprint "eagle-import:R0603")
      (libsource (lib "eagle-import") (part "R-EU_R0603"))
    )
    (comp (ref "R1113")
      (value "100kR")
      (footprint "eagle-import:R0603")
      (libsource (lib "eagle-import") (part "R-EU_R0603"))
    )
    (comp (ref "R1114")
      (value "15kR")
      (footprint "eagle-import:R0603")
      (libsource (lib "eagle-import") (part "R-EU_R0603"))
    )
    (comp (ref "R1115")
      (value "68kR")
      (footprint "eagle-import:R0603")
      (libsource (lib "eagle-import") (part "R-EU_R0603"))
    )
    (comp (ref "R1131")
      (value "4.02kR")
      (footprint "eagle-import:R0603")
      (libsource (lib "eagle-import") (part "R-EU_R0603"))
    )
    (comp (ref "R1132")
      (value "6.04kR")
      (footprint "eagle-import:R0603")
      (libsource (lib "eagle-import") (part "R-EU_R0603"))
    )
    (comp (ref "R1141")
      (value "4.02kR")
      (footprint "eagle-import:R0603")
      (libsource (lib "eagle-import") (part "R-EU_R0603"))
    )
    (comp (ref "R1142")
      (value "2.0kR")
      (footprint "eagle-import:R0603")
      (libsource (lib "eagle-import") (part "R-EU_R0603"))
    )
    (comp (ref "U101")
      (value "ATXMEGA256A3BU-AU")
      (footprint "eagle-import:QFP80P1600X1600X120-64N")
      (libsource (lib "eagle-import") (part "ATXMEGA256A3BU-AU"))
    )
    (comp (ref "U1111")
      (value "LM2831YMF")
      (footprint "eagle-import:SOT95P280X145-5N")
      (fields (field (name "MPN") "LM2831YMF/NOPB"))
      (libsource (lib "eagle-import") (part "LM2831YMF"))
    )
    (comp (ref "U1121")
      (value "LM4120IM5-3.0")
      (footprint "eagle-import:SOT95P285X120-5N")
      (libsource (lib "eagle-import") (part "LM4120IM5-3.0"))
    )
    (comp (ref "C1001")
      (value "100nF")
      (footprint "eagle-import:C0603")
      (libsource (lib "eagle-import") (part "C-EUC0603"))
    )
    (comp (ref "C1002")
      (value "100nF")
      (footprint "eagle-import:C0603")
      (libsource (lib "eagle-import") (part "C-EUC0603"))
    )
    (comp (ref "C1011")
      (value "100pF")
      (footprint "eagle-import:C0603")
      (libsource (lib "eagle-import") (part "C-EUC0603"))
    )
    (comp (ref "C1012")
      (value "100nF")
      (footprint "eagle-import:C0603")
      (libsource (lib "eagle-import") (part "C-EUC0603"))
    )
    (comp (ref "R1001")
      (value "100kR")
      (footprint "eagle-import:R0603")
      (libsource (lib "eagle-import") (part "R-EU_R0603"))
    )
    (comp (ref "R1002")
      (value "10kR")
      (footprint "eagle-import:R0603")
      (libsource (lib "eagle-import") (part "R-EU_R0603"))
    )
    (comp (ref "R1011")
      (value "100kR")
      (footprint "eagle-import:R0603")
      (libsource (lib "eagle-import") (part "R-EU_R0603"))
    )
    (comp (ref "R1012")
      (value "470kR")
      (footprint "eagle-import:R0603")
      (libsource (lib "eagle-import") (part "R-EU_R0603"))
    )
    (comp (ref "R1013")
      (value "47R")
      (footprint "eagle-import:R0603")
      (libsource (lib "eagle-import") (part "R-EU_R0603"))
    )
    (comp (ref "R1021")
      (value "27R")
      (footprint "eagle-import:R0603")
      (libsource (lib "eagle-import") (part "R-EU_R0603"))
    )
    (comp (ref "U1001")
      (value "CFPT-141-20MHZ")
      (footprint "eagle-import:CFPT-141")
      (fields (field (name "MF") "IQD-FREQUENCY-PRODUCTS") (field (name "MPN") "LFTVXO022175"))
      (libsource (lib "eagle-import") (part "CFPT-141-20MHZ"))
    )
    (comp (ref "U1011")
      (value "OPA354")
      (footprint "eagle-import:SOT-23-5")
      (fields (field (name "MPN") "OPA354AIDBVT"))
      (libsource (lib "eagle-import") (part "OPA354"))
    )
    (comp (ref "U1021")
      (value "OPA354")
      (footprint "eagle-import:SOT-23-5")
      (fields (field (name "MPN") "OPA354AIDBVT"))
      (libsource (lib "eagle-import") (part "OPA354"))
    )
    (comp (ref "C601")
      (value "100nF")
      (footprint "eagle-import:C0603")
      (libsource (lib "eagle-import") (part "C-EUC0603"))
    )
    (comp (ref "C611")
      (value "100nF")
      (footprint "eagle-import:C0603")
      (libsource (lib "eagle-import") (part "C-EUC0603"))
    )
    (comp (ref "C612")
      (value "100nF")
      (footprint "eagle-import:C0603")
      (libsource (lib "eagle-import") (part "C-EUC0603"))
    )
    (comp (ref "C681")
      (value "68pF")
      (footprint "eagle-import:C0603")
      (libsource (lib "eagle-import") (part "C-EUC0603"))
    )
    (comp (ref "C686")
      (value "18pF")
      (footprint "eagle-import:C0603")
      (libsource (lib "eagle-import") (part "C-EUC0603"))
    )
    (comp (ref "L671")
      (value "22nH")
      (footprint "eagle-import:R0603")
      (libsource (lib "eagle-import") (part "R-EU_R0603"))
    )
    (comp (ref "L681")
      (value "150nH")
      (footprint "eagle-import:R0603")
      (libsource (lib "eagle-import") (part "R-EU_R0603"))
    )
    (comp (ref "L682")
      (value "68nH")
      (footprint "eagle-import:R0603")
      (libsource (lib "eagle-import") (part "R-EU_R0603"))
    )
    (comp (ref "L686")
      (value "150nH")
      (footprint "eagle-import:R0603")
      (libsource (lib "eagle-import") (part "R-EU_R0603"))
    )
    (comp (ref "Q651")
      (value "ABM3B-16MHZ-10-R50-1-U")
      (footprint "eagle-import:ABM03B")
      (libsource (lib "eagle-import") (part "ABM03B-16.000MHZ"))
    )
    (comp (ref "U601")
      (value "AX5243")
      (footprint "eagle-import:QFN20-4X4-0P5-PAD")
      (libsource (lib "eagle-import") (part "AX5243"))
    )
    (comp (ref "X685")
      (value "SMA_CON")
      (footprint "eagle-import:SMA_SMT_AMPHENOL_901-143")
      (fields (field (name "MPN") "901-143"))
      (libsource (lib "eagle-import") (part "SMA_SMT_AMPHENOL-901-143"))
    )
    (comp (ref "FM1201")
      (value "FIDUCIAL_MARK_1MM")
      (footprint "eagle-import:FIDUCIAL_MARK_1MM")
      (libsource (lib "eagle-import") (part "FIDUCIAL_MARK_1MM"))
    )
    (comp (ref "FM1202")
      (value "FIDUCIAL_MARK_1MM")
      (footprint "eagle-import:FIDUCIAL_MARK_1MM")
      (libsource (lib "eagle-import") (part "FIDUCIAL_MARK_1MM"))
    )
    (comp (ref "FM1203")
      (value "FIDUCIAL_MARK_1MM")
      (footprint "eagle-import:FIDUCIAL_MARK_1MM")
      (libsource (lib "eagle-import") (part "FIDUCIAL_MARK_1MM"))
    )
    (comp (ref "FM1204")
      (value "FIDUCIAL_MARK_1MM")
      (footprint "eagle-import:FIDUCIAL_MARK_1MM")
      (libsource (lib "eagle-import") (part "FIDUCIAL_MARK_1MM"))
    )
    (comp (ref "H1201")
      (value "MOUNT-PAD-ROUND2.8")
      (footprint "eagle-import:2,8-PAD")
      (libsource (lib "eagle-import") (part "MOUNT-PAD-ROUND2.8"))
    )
    (comp (ref "H1203")
      (value "MOUNT-PAD-ROUND2.8")
      (footprint "eagle-import:2,8-PAD")
      (libsource (lib "eagle-import") (part "MOUNT-PAD-ROUND2.8"))
    )
    (comp (ref "H1204")
      (value "MOUNT-PAD-ROUND2.8")
      (footprint "eagle-import:2,8-PAD")
      (libsource (lib "eagle-import") (part "MOUNT-PAD-ROUND2.8"))
    )
    (comp (ref "C501")
      (value "100nF")
      (footprint "eagle-import:C0603")
      (libsource (lib "eagle-import") (part "C-EUC0603"))
    )
    (comp (ref "U501")
      (value "SHT31-DIS")
      (footprint "eagle-import:DFN8_SHT")
      (libsource (lib "eagle-import") (part "SHT31-DIS"))
    )
    (comp (ref "C401")
      (value "100nF")
      (footprint "eagle-import:C0603")
      (libsource (lib "eagle-import") (part "C-EUC0603"))
    )
    (comp (ref "R401")
      (value "10kR")
      (footprint "eagle-import:R0603")
      (libsource (lib "eagle-import") (part "R-EU_R0603"))
    )
    (comp (ref "R402")
      (value "10kR")
      (footprint "eagle-import:R0603")
      (libsource (lib "eagle-import") (part "R-EU_R0603"))
    )
    (comp (ref "U401")
      (value "MS5607-02BA03")
      (footprint "eagle-import:MS5607-02BA")
      (libsource (lib "eagle-import") (part "MS5607-02BA03"))
    )
    (comp (ref "C201")
      (value "100pF")
      (footprint "eagle-import:C0603")
      (libsource (lib "eagle-import") (part "C-EUC0603"))
    )
    (comp (ref "C251")
      (value "100pF")
      (footprint "eagle-import:C0603")
      (libsource (lib "eagle-import") (part "C-EUC0603"))
    )
    (comp (ref "C271")
      (value "C-EUC0603")
      (footprint "eagle-import:C0603")
      (libsource (lib "eagle-import") (part "C-EUC0603"))
    )
    (comp (ref "C272")
      (value "C-EUC0603")
      (footprint "eagle-import:C0603")
      (libsource (lib "eagle-import") (part "C-EUC0603"))
    )
    (comp (ref "C281")
      (value "C-EUC0603")
      (footprint "eagle-import:C0603")
      (libsource (lib "eagle-import") (part "C-EUC0603"))
    )
    (comp (ref "C282")
      (value "C-EUC0603")
      (footprint "eagle-import:C0603")
      (libsource (lib "eagle-import") (part "C-EUC0603"))
    )
    (comp (ref "C291")
      (value "C-EUC0603")
      (footprint "eagle-import:C0603")
      (libsource (lib "eagle-import") (part "C-EUC0603"))
    )
    (comp (ref "C292")
      (value "C-EUC0603")
      (footprint "eagle-import:C0603")
      (libsource (lib "eagle-import") (part "C-EUC0603"))
    )
    (comp (ref "D201")
      (value "BZX84-5V1")
      (footprint "eagle-import:TO236")
      (libsource (lib "eagle-import") (part "BZX84CSMD"))
    )
    (comp (ref "JP201")
      (value "POW")
      (footprint "eagle-import:1X02")
      (libsource (lib "eagle-import") (part "HEADER-1X2"))
    )
    (comp (ref "L291")
      (value "WE-CBF_300R")
      (footprint "eagle-import:L3216C")
      (libsource (lib "eagle-import") (part "L-EUL3216C"))
    )
    (comp (ref "R211")
      (value "10kR")
      (footprint "eagle-import:R0603")
      (libsource (lib "eagle-import") (part "R-EU_R0603"))
    )
    (comp (ref "R212")
      (value "10kR")
      (footprint "eagle-import:R0603")
      (libsource (lib "eagle-import") (part "R-EU_R0603"))
    )
    (comp (ref "R221")
      (value "68R")
      (footprint "eagle-import:R0603")
      (libsource (lib "eagle-import") (part "R-EU_R0603"))
    )
    (comp (ref "R222")
      (value "68R")
      (footprint "eagle-import:R0603")
      (libsource (lib "eagle-import") (part "R-EU_R0603"))
    )
    (comp (ref "R223")
      (value "68R")
      (footprint "eagle-import:R0603")
      (libsource (lib "eagle-import") (part "R-EU_R0603"))
    )
    (comp (ref "R224")
      (value "68R")
      (footprint "eagle-import:R0603")
      (libsource (lib "eagle-import") (part "R-EU_R0603"))
    )
    (comp (ref "R231")
      (value "68R")
      (footprint "eagle-import:R0603")
      (libsource (lib "eagle-import") (part "R-EU_R0603"))
    )
    (comp (ref "R232")
      (value "68R")
      (footprint "eagle-import:R0603")
      (libsource (lib "eagle-import") (part "R-EU_R0603"))
    )
    (comp (ref "R233")
      (value "68R")
      (footprint "eagle-import:R0603")
      (libsource (lib "eagle-import") (part "R-EU_R0603"))
    )
    (comp (ref "R234")
      (value "68R")
      (footprint "eagle-import:R0603")
      (libsource (lib "eagle-import") (part "R-EU_R0603"))
    )
    (comp (ref "R241")
      (value "68R")
      (footprint "eagle-import:R0603")
      (libsource (lib "eagle-import") (part "R-EU_R0603"))
    )
    (comp (ref "R251")
      (value "68R")
      (footprint "eagle-import:R0603")
      (libsource (lib "eagle-import") (part "R-EU_R0603"))
    )
    (comp (ref "R271")
      (value "R-EU_R0603")
      (footprint "eagle-import:R0603")
      (libsource (lib "eagle-import") (part "R-EU_R0603"))
    )
    (comp (ref "R281")
      (value "R-EU_R0603")
      (footprint "eagle-import:R0603")
      (libsource (lib "eagle-import") (part "R-EU_R0603"))
    )
    (comp (ref "R291")
      (value "R-EU_R0603")
      (footprint "eagle-import:R0603")
      (libsource (lib "eagle-import") (part "R-EU_R0603"))
    )
    (comp (ref "RPOLY291")
      (value "50mA/150mA")
      (footprint "eagle-import:R1210")
      (libsource (lib "eagle-import") (part "R-EU_R1210"))
    )
    (comp (ref "U201")
      (value "SIM808")
      (footprint "eagle-import:SIM808")
      (libsource (lib "eagle-import") (part "SIM808"))
    )
    (comp (ref "X291")
      (value "MCX-J-P-X-RA-SM1")
      (footprint "eagle-import:MCX-J-P-X-RA-SM1")
      (libsource (lib "eagle-import") (part "MCX-J-P-X-RA-SM1"))
    )
    (comp (ref "C701")
      (value "1nF")
      (footprint "eagle-import:C0603")
      (libsource (lib "eagle-import") (part "C-EUC0603"))
    )
    (comp (ref "C711")
      (value "100nF")
      (footprint "eagle-import:C0603")
      (libsource (lib "eagle-import") (part "C-EUC0603"))
    )
    (comp (ref "C712")
      (value "47uF")
      (footprint "eagle-import:C0805")
      (libsource (lib "eagle-import") (part "C-EUC0805"))
    )
    (comp (ref "D721")
      (value "BZX84-3V6")
      (footprint "eagle-import:TO236")
      (libsource (lib "eagle-import") (part "BZX84CSMD"))
    )
    (comp (ref "D722")
      (value "BZX84-3V6")
      (footprint "eagle-import:TO236")
      (libsource (lib "eagle-import") (part "BZX84CSMD"))
    )
    (comp (ref "R701")
      (value "330kR")
      (footprint "eagle-import:R0603")
      (libsource (lib "eagle-import") (part "R-EU_R0603"))
    )
    (comp (ref "R721")
      (value "1.5kR")
      (footprint "eagle-import:R0603")
      (libsource (lib "eagle-import") (part "R-EU_R0603"))
    )
    (comp (ref "R722")
      (value "68R")
      (footprint "eagle-import:R0603")
      (libsource (lib "eagle-import") (part "R-EU_R0603"))
    )
    (comp (ref "R723")
      (value "68R")
      (footprint "eagle-import:R0603")
      (libsource (lib "eagle-import") (part "R-EU_R0603"))
    )
    (comp (ref "R724")
      (value "1MR")
      (footprint "eagle-import:R0603")
      (libsource (lib "eagle-import") (part "R-EU_R0603"))
    )
    (comp (ref "R725")
      (value "68R")
      (footprint "eagle-import:R0603")
      (libsource (lib "eagle-import") (part "R-EU_R0603"))
    )
    (comp (ref "RPOLY711")
      (value "0.5A/1.0A")
      (footprint "eagle-import:M1206")
      (libsource (lib "eagle-import") (part "R-EU_M1206"))
    )
    (comp (ref "X701")
      (value "MOLEX_105017-0001")
      (footprint "eagle-import:USB-B-MICRO-SMD_MOLEX-105017-0001")
      (libsource (lib "eagle-import") (part "USB_MICRO-B_MOLEX"))
    )
    (comp (ref "C901")
      (value "100uF")
      (footprint "eagle-import:C0805")
      (libsource (lib "eagle-import") (part "C-EUC0805"))
    )
    (comp (ref "RPOLY901")
      (value "1.1A/2.2A")
      (footprint "eagle-import:M1206")
      (libsource (lib "eagle-import") (part "R-EU_M1206"))
    )
    (comp (ref "X901")
      (value "JST_S3B-XH-A")
      (footprint "eagle-import:JST_S3B-XH-A")
      (libsource (lib "eagle-import") (part "JST_S3B-XH-A"))
    )
    (comp (ref "C101")
      (value "100nF")
      (footprint "eagle-import:C0603")
      (libsource (lib "eagle-import") (part "C-EUC0603"))
    )
    (comp (ref "C141")
      (value "100pF")
      (footprint "eagle-import:C0603")
      (libsource (lib "eagle-import") (part "C-EUC0603"))
    )
    (comp (ref "Q101")
      (value "ABS07-32.768KHZ")
      (footprint "eagle-import:ABS07")
      (fields (field (name "MANUFACTURER") "ABS07-32.768KHZ-1-T"))
      (libsource (lib "eagle-import") (part "ABS07-32.768KHZ"))
    )
    (comp (ref "R111")
      (value "0R")
      (footprint "eagle-import:R0805")
      (libsource (lib "eagle-import") (part "R-EU_R0805"))
    )
    (comp (ref "R112")
      (value "10kR")
      (footprint "eagle-import:R0603")
      (libsource (lib "eagle-import") (part "R-EU_R0603"))
    )
    (comp (ref "R131")
      (value "68R")
      (footprint "eagle-import:R0603")
      (libsource (lib "eagle-import") (part "R-EU_R0603"))
    )
    (comp (ref "R132")
      (value "68R")
      (footprint "eagle-import:R0603")
      (libsource (lib "eagle-import") (part "R-EU_R0603"))
    )
    (comp (ref "R141")
      (value "68R")
      (footprint "eagle-import:R0603")
      (libsource (lib "eagle-import") (part "R-EU_R0603"))
    )
    (comp (ref "R142")
      (value "68R")
      (footprint "eagle-import:R0603")
      (libsource (lib "eagle-import") (part "R-EU_R0603"))
    )
    (comp (ref "R151")
      (value "68R")
      (footprint "eagle-import:R0603")
      (libsource (lib "eagle-import") (part "R-EU_R0603"))
    )
    (comp (ref "R161")
      (value "4.7kR")
      (footprint "eagle-import:R0603")
      (libsource (lib "eagle-import") (part "R-EU_R0603"))
    )
    (comp (ref "R162")
      (value "68R")
      (footprint "eagle-import:R0603")
      (libsource (lib "eagle-import") (part "R-EU_R0603"))
    )
    (comp (ref "R163")
      (value "68R")
      (footprint "eagle-import:R0603")
      (libsource (lib "eagle-import") (part "R-EU_R0603"))
    )
    (comp (ref "R171")
      (value "68R")
      (footprint "eagle-import:R0603")
      (libsource (lib "eagle-import") (part "R-EU_R0603"))
    )
    (comp (ref "R172")
      (value "68R")
      (footprint "eagle-import:R0603")
      (libsource (lib "eagle-import") (part "R-EU_R0603"))
    )
    (comp (ref "R173")
      (value "68R")
      (footprint "eagle-import:R0603")
      (libsource (lib "eagle-import") (part "R-EU_R0603"))
    )
    (comp (ref "X111")
      (value "AVR-JTAG-10")
      (footprint "eagle-import:2X05")
      (libsource (lib "eagle-import") (part "AVR-JTAG-10"))
    )
    (comp (ref "X121")
      (value "MOLEX_90130_2X03")
      (footprint "eagle-import:MOLEX_90130_2X03")
      (libsource (lib "eagle-import") (part "MOLEX_90130_2X03"))
    )
    (comp (ref "X131")
      (value "HEADER-2X3")
      (footprint "eagle-import:2X03")
      (libsource (lib "eagle-import") (part "HEADER-2X3"))
    )
    (comp (ref "X181")
      (value "HEADER-2X3")
      (footprint "eagle-import:2X03")
      (libsource (lib "eagle-import") (part "HEADER-2X3"))
    )
    (comp (ref "X801")
      (value "MICROSIM-8P_SDCARD-8P_MOLEX-104642-1610")
      (footprint "eagle-import:MICROSIM-8P_SDCARD-8P_MOLEX-104642-1610")
      (fields (field (name "MPN") "MOLEX-104642-1610"))
      (libsource (lib "eagle-import") (part "MICROSIM-8P_SDCARD-8P_MOLEX-104642-1610"))
    )
  )
  (nets
    (net (code "1") (name "+3V0") (class "Default")
      (node (ref "C1002") (pin "1") (pinfunction "1_1") (pintype "passive"))
      (node (ref "C101") (pin "1") (pinfunction "1_1") (pintype "passive"))
      (node (ref "C251") (pin "1") (pinfunction "1_1") (pintype "passive"))
      (node (ref "R1142") (pin "2") (pinfunction "2_2") (pintype "passive"))
      (node (ref "U1001") (pin "4") (pinfunction "VCC_3V0_4") (pintype "power_in"))
      (node (ref "U101") (pin "51") (pinfunction "VBAT_51") (pintype "power_in"))
      (node (ref "U1121") (pin "5") (pinfunction "VOUT_5") (pintype "power_in"))
      (node (ref "U201") (pin "17") (pinfunction "VRTC_17") (pintype "power_in"))
    )
    (net (code "2") (name "+3V3") (class "Default")
      (node (ref "C1012") (pin "1") (pinfunction "1_1") (pintype "passive"))
      (node (ref "C1112") (pin "1") (pinfunction "1_1") (pintype "passive"))
      (node (ref "C1113") (pin "1") (pinfunction "1_1") (pintype "passive"))
      (node (ref "C191") (pin "1") (pinfunction "1_1") (pintype "passive"))
      (node (ref "C192") (pin "1") (pinfunction "1_1") (pintype "passive"))
      (node (ref "C193") (pin "1") (pinfunction "1_1") (pintype "passive"))
      (node (ref "C194") (pin "1") (pinfunction "1_1") (pintype "passive"))
      (node (ref "C195") (pin "1") (pinfunction "1_1") (pintype "passive"))
      (node (ref "C301") (pin "1") (pinfunction "1_1") (pintype "passive"))
      (node (ref "C401") (pin "1") (pinfunction "1_1") (pintype "passive"))
      (node (ref "C501") (pin "1") (pinfunction "1_1") (pintype "passive"))
      (node (ref "C601") (pin "1") (pinfunction "1_1") (pintype "passive"))
      (node (ref "L1111") (pin "1") (pinfunction "1_1") (pintype "passive"))
      (node (ref "L191") (pin "2") (pinfunction "2_2") (pintype "passive"))
      (node (ref "R1012") (pin "2") (pinfunction "2_2") (pintype "passive"))
      (node (ref "R111") (pin "2") (pinfunction "2_2") (pintype "passive"))
      (node (ref "R1115") (pin "2") (pinfunction "2_2") (pintype "passive"))
      (node (ref "R112") (pin "2") (pinfunction "2_2") (pintype "passive"))
      (node (ref "R211") (pin "1") (pinfunction "1_1") (pintype "passive"))
      (node (ref "R212") (pin "1") (pinfunction "1_1") (pintype "passive"))
      (node (ref "R401") (pin "2") (pinfunction "2_2") (pintype "passive"))
      (node (ref "R402") (pin "2") (pinfunction "2_2") (pintype "passive"))
      (node (ref "RPOLY291") (pin "2") (pinfunction "2_2") (pintype "passive"))
      (node (ref "U101") (pin "15") (pinfunction "VCC_1_15") (pintype "power_in"))
      (node (ref "U101") (pin "25") (pinfunction "VCC_2_25") (pintype "power_in"))
      (node (ref "U101") (pin "35") (pinfunction "VCC_3_35") (pintype "power_in"))
      (node (ref "U101") (pin "45") (pinfunction "VCC_4_45") (pintype "power_in"))
      (node (ref "U101") (pin "53") (pinfunction "VCC_5_53") (pintype "power_in"))
      (node (ref "U1011") (pin "5") (pinfunction "V+_5") (pintype "power_in"))
      (node (ref "U1021") (pin "5") (pinfunction "V+_5") (pintype "power_in"))
      (node (ref "U301") (pin "1") (pinfunction "VDDIO_1") (pintype "power_in"))
      (node (ref "U301") (pin "13") (pinfunction "VDD_13") (pintype "power_in"))
      (node (ref "U301") (pin "22") (pinfunction "~{CS}_22") (pintype "input"))
      (node (ref "U301") (pin "8") (pinfunction "VDDIO_8") (pintype "power_in"))
      (node (ref "U401") (pin "1") (pinfunction "VDD_1") (pintype "power_in"))
      (node (ref "U401") (pin "2") (pinfunction "PS_2") (pintype "input"))
      (node (ref "U401") (pin "4") (pinfunction "CSB_~{ADDR}_4") (pintype "input"))
      (node (ref "U501") (pin "5") (pinfunction "VDD_5") (pintype "power_in"))
      (node (ref "U601") (pin "16") (pinfunction "VDD_IO_16") (pintype "power_in"))
      (node (ref "X111") (pin "7") (pinfunction "7_7") (pintype "passive"))
      (node (ref "X121") (pin "6") (pinfunction "6_6") (pintype "passive"))
      (node (ref "X131") (pin "2") (pinfunction "2_2") (pintype "passive"))
    )
    (net (code "3") (name "+5V") (class "Default")
      (node (ref "C711") (pin "1") (pinfunction "1_1") (pintype "passive"))
      (node (ref "C712") (pin "1") (pinfunction "1_1") (pintype "passive"))
      (node (ref "D1121") (pin "A") (pinfunction "A_A") (pintype "passive"))
      (node (ref "JP201") (pin "1") (pinfunction "1_1") (pintype "passive"))
      (node (ref "R1112") (pin "2") (pinfunction "2_2") (pintype "passive"))
      (node (ref "RPOLY711") (pin "2") (pinfunction "2_2") (pintype "passive"))
      (node (ref "X121") (pin "4") (pinfunction "4_4") (pintype "passive"))
    )
    (net (code "4") (name "AD_3V0") (class "Default")
      (node (ref "R1141") (pin "2") (pinfunction "2_2") (pintype "passive"))
      (node (ref "R1142") (pin "1") (pinfunction "1_1") (pintype "passive"))
      (node (ref "U101") (pin "62") (pinfunction "PA0_62") (pintype "bidirectional"))
    )
    (net (code "5") (name "AD_5V0") (class "Default")
      (node (ref "R1111") (pin "2") (pinfunction "2_2") (pintype "passive"))
      (node (ref "R1112") (pin "1") (pinfunction "1_1") (pintype "passive"))
      (node (ref "U101") (pin "64") (pinfunction "PA2_64") (pintype "bidirectional"))
    )
    (net (code "6") (name "AD_VBAT") (class "Default")
      (node (ref "R1131") (pin "1") (pinfunction "1_1") (pintype "passive"))
      (node (ref "R1132") (pin "2") (pinfunction "2_2") (pintype "passive"))
      (node (ref "U101") (pin "1") (pinfunction "PA3_1") (pintype "bidirectional"))
    )
    (net (code "7") (name "AD_VCTCXO") (class "Default")
      (node (ref "R1021") (pin "2") (pinfunction "2_2") (pintype "passive"))
      (node (ref "U101") (pin "63") (pinfunction "PA1_63") (pintype "bidirectional"))
      (node (ref "U1021") (pin "1") (pinfunction "OUT_1") (pintype "output"))
    )
    (net (code "8") (name "AVCC") (class "Default")
      (node (ref "C196") (pin "1") (pinfunction "1_1") (pintype "passive"))
      (node (ref "L191") (pin "1") (pinfunction "1_1") (pintype "passive"))
      (node (ref "U101") (pin "61") (pinfunction "AVCC_61") (pintype "power_in"))
    )
    (net (code "9") (name "AX_ANT") (class "Default")
      (node (ref "C686") (pin "2") (pinfunction "2_2") (pintype "passive"))
      (node (ref "L682") (pin "2") (pinfunction "2_2") (pintype "passive"))
      (node (ref "X685") (pin "1") (pinfunction "1_1") (pintype "passive"))
    )
    (net (code "10") (name "AX_ANTN") (class "Default")
      (node (ref "C686") (pin "1") (pinfunction "1_1") (pintype "passive"))
      (node (ref "L686") (pin "2") (pinfunction "2_2") (pintype "passive"))
      (node (ref "U601") (pin "4") (pinfunction "ANTN_4") (pintype "passive"))
    )
    (net (code "11") (name "AX_ANTP") (class "Default")
      (node (ref "C681") (pin "1") (pinfunction "1_1") (pintype "passive"))
      (node (ref "L681") (pin "1") (pinfunction "1_1") (pintype "passive"))
      (node (ref "U601") (pin "3") (pinfunction "ANTP_3") (pintype "passive"))
    )
    (net (code "12") (name "AX_ANT_I") (class "Default")
      (node (ref "C681") (pin "2") (pinfunction "2_2") (pintype "passive"))
      (node (ref "L682") (pin "1") (pinfunction "1_1") (pintype "passive"))
    )
    (net (code "13") (name "AX_CLK") (class "Default")
      (node (ref "U101") (pin "23") (pinfunction "PC7_23") (pintype "bidirectional"))
      (node (ref "U601") (pin "11") (pinfunction "CLK_11") (pintype "input"))
    )
    (net (code "14") (name "AX_IRQ") (class "Default")
      (node (ref "U101") (pin "19") (pinfunction "PC3_19") (pintype "bidirectional"))
      (node (ref "U601") (pin "14") (pinfunction "IRQ_14") (pintype "bidirectional"))
    )
    (net (code "15") (name "AX_L1") (class "Default")
      (node (ref "L671") (pin "1") (pinfunction "1_1") (pintype "passive"))
      (node (ref "U601") (pin "8") (pinfunction "L1_8") (pintype "passive"))
    )
    (net (code "16") (name "AX_L2") (class "Default")
      (node (ref "L671") (pin "2") (pinfunction "2_2") (pintype "passive"))
      (node (ref "U601") (pin "7") (pinfunction "L2_7") (pintype "passive"))
    )
    (net (code "17") (name "AX_MISO") (class "Default")
      (node (ref "U101") (pin "22") (pinfunction "PC6_22") (pintype "bidirectional"))
      (node (ref "U601") (pin "12") (pinfunction "MISO_12") (pintype "output"))
    )
    (net (code "18") (name "AX_MOSI") (class "Default")
      (node (ref "U101") (pin "21") (pinfunction "PC5_21") (pintype "bidirectional"))
      (node (ref "U601") (pin "13") (pinfunction "MOSI_13") (pintype "input"))
    )
    (net (code "19") (name "AX_SEL") (class "Default")
      (node (ref "U101") (pin "20") (pinfunction "PC4_20") (pintype "bidirectional"))
      (node (ref "U601") (pin "10") (pinfunction "SEL_10") (pintype "input"))
    )
    (net (code "20") (name "BT_ANT") (class "Default")
      (node (ref "C282") (pin "1") (pinfunction "1_1") (pintype "passive"))
      (node (ref "R281") (pin "2") (pinfunction "2_2") (pintype "passive"))
    )
    (net (code "21") (name "BT_RF") (class "Default")
      (node (ref "C281") (pin "1") (pinfunction "1_1") (pintype "passive"))
      (node (ref "R281") (pin "1") (pinfunction "1_1") (pintype "passive"))
      (node (ref "U201") (pin "53") (pinfunction "ANT_BT_53") (pintype "bidirectional"))
    )
    (net (code "22") (name "CTS1") (class "Default")
      (node (ref "R173") (pin "1") (pinfunction "1_1") (pintype "passive"))
      (node (ref "U101") (pin "55") (pinfunction "PF7_55") (pintype "bidirectional"))
    )
    (net (code "23") (name "DCD1") (class "Default")
      (node (ref "R171") (pin "1") (pinfunction "1_1") (pintype "passive"))
      (node (ref "U101") (pin "47") (pinfunction "PF1_47") (pintype "bidirectional"))
    )
    (net (code "24") (name "DTR1") (class "Default")
      (node (ref "R222") (pin "1") (pinfunction "1_1") (pintype "passive"))
      (node (ref "U101") (pin "46") (pinfunction "PF0_46") (pintype "bidirectional"))
    )
    (net (code "25") (name "EN") (class "Default")
      (node (ref "R1113") (pin "2") (pinfunction "2_2") (pintype "passive"))
      (node (ref "U1111") (pin "4") (pinfunction "EN_4") (pintype "input"))
    )
    (net (code "26") (name "FB") (class "Default")
      (node (ref "R1114") (pin "2") (pinfunction "2_2") (pintype "passive"))
      (node (ref "R1115") (pin "1") (pinfunction "1_1") (pintype "passive"))
      (node (ref "U1111") (pin "3") (pinfunction "FB_3") (pintype "input"))
    )
    (net (code "27") (name "GND") (class "Default")
      (node (ref "C1001") (pin "2") (pinfunction "2_2") (pintype "passive"))
      (node (ref "C1002") (pin "2") (pinfunction "2_2") (pintype "passive"))
      (node (ref "C101") (pin "2") (pinfunction "2_2") (pintype "passive"))
      (node (ref "C1011") (pin "2") (pinfunction "2_2") (pintype "passive"))
      (node (ref "C1012") (pin "2") (pinfunction "2_2") (pintype "passive"))
      (node (ref "C1111") (pin "2") (pinfunction "2_2") (pintype "passive"))
      (node (ref "C1112") (pin "2") (pinfunction "2_2") (pintype "passive"))
      (node (ref "C1113") (pin "2") (pinfunction "2_2") (pintype "passive"))
      (node (ref "C1121") (pin "2") (pinfunction "2_2") (pintype "passive"))
      (node (ref "C141") (pin "2") (pinfunction "2_2") (pintype "passive"))
      (node (ref "C191") (pin "2") (pinfunction "2_2") (pintype "passive"))
      (node (ref "C192") (pin "2") (pinfunction "2_2") (pintype "passive"))
      (node (ref "C193") (pin "2") (pinfunction "2_2") (pintype "passive"))
      (node (ref "C194") (pin "2") (pinfunction "2_2") (pintype "passive"))
      (node (ref "C195") (pin "2") (pinfunction "2_2") (pintype "passive"))
      (node (ref "C196") (pin "2") (pinfunction "2_2") (pintype "passive"))
      (node (ref "C201") (pin "2") (pinfunction "2_2") (pintype "passive"))
      (node (ref "C251") (pin "2") (pinfunction "2_2") (pintype "passive"))
      (node (ref "C271") (pin "2") (pinfunction "2_2") (pintype "passive"))
      (node (ref "C272") (pin "2") (pinfunction "2_2") (pintype "passive"))
      (node (ref "C281") (pin "2") (pinfunction "2_2") (pintype "passive"))
      (node (ref "C282") (pin "2") (pinfunction "2_2") (pintype "passive"))
      (node (ref "C291") (pin "2") (pinfunction "2_2") (pintype "passive"))
      (node (ref "C292") (pin "2") (pinfunction "2_2") (pintype "passive"))
      (node (ref "C301") (pin "2") (pinfunction "2_2") (pintype "passive"))
      (node (ref "C302") (pin "2") (pinfunction "2_2") (pintype "passive"))
      (node (ref "C401") (pin "2") (pinfunction "2_2") (pintype "passive"))
      (node (ref "C501") (pin "2") (pinfunction "2_2") (pintype "passive"))
      (node (ref "C601") (pin "2") (pinfunction "2_2") (pintype "passive"))
      (node (ref "C611") (pin "2") (pinfunction "2_2") (pintype "passive"))
      (node (ref "C612") (pin "2") (pinfunction "2_2") (pintype "passive"))
      (node (ref "C701") (pin "2") (pinfunction "2_2") (pintype "passive"))
      (node (ref "C711") (pin "2") (pinfunction "2_2") (pintype "passive"))
      (node (ref "C712") (pin "2") (pinfunction "2_2") (pintype "passive"))
      (node (ref "C901") (pin "2") (pinfunction "2_2") (pintype "passive"))
      (node (ref "D1111") (pin "A") (pinfunction "A_A") (pintype "passive"))
      (node (ref "D201") (pin "A") (pinfunction "A_A") (pintype "passive"))
      (node (ref "D721") (pin "A") (pinfunction "A_A") (pintype "passive"))
      (node (ref "D722") (pin "A") (pinfunction "A_A") (pintype "passive"))
      (node (ref "H1201") (pin "B2,8") (pinfunction "MOUNT_B2,8") (pintype "passive"))
      (node (ref "H1203") (pin "B2,8") (pinfunction "MOUNT_B2,8") (pintype "passive"))
      (node (ref "H1204") (pin "B2,8") (pinfunction "MOUNT_B2,8") (pintype "passive"))
      (node (ref "L681") (pin "2") (pinfunction "2_2") (pintype "passive"))
      (node (ref "L686") (pin "1") (pinfunction "1_1") (pintype "passive"))
      (node (ref "Q651") (pin "2") (pinfunction "3_2") (pintype "passive"))
      (node (ref "Q651") (pin "4") (pinfunction "3_4") (pintype "passive"))
      (node (ref "R1011") (pin "1") (pinfunction "1_1") (pintype "passive"))
      (node (ref "R1111") (pin "1") (pinfunction "1_1") (pintype "passive"))
      (node (ref "R1114") (pin "1") (pinfunction "1_1") (pintype "passive"))
      (node (ref "R1131") (pin "2") (pinfunction "2_2") (pintype "passive"))
      (node (ref "R1141") (pin "1") (pinfunction "1_1") (pintype "passive"))
      (node (ref "R701") (pin "2") (pinfunction "2_2") (pintype "passive"))
      (node (ref "R724") (pin "2") (pinfunction "2_2") (pintype "passive"))
      (node (ref "U1001") (pin "2") (pinfunction "GND_2") (pintype "power_in"))
      (node (ref "U101") (pin "14") (pinfunction "GND_1_14") (pintype "passive"))
      (node (ref "U101") (pin "24") (pinfunction "GND_2_24") (pintype "passive"))
      (node (ref "U101") (pin "34") (pinfunction "GND_3_34") (pintype "passive"))
      (node (ref "U101") (pin "44") (pinfunction "GND_4_44") (pintype "passive"))
      (node (ref "U101") (pin "52") (pinfunction "GND_5_52") (pintype "passive"))
      (node (ref "U101") (pin "60") (pinfunction "GND_6_60") (pintype "passive"))
      (node (ref "U1011") (pin "2") (pinfunction "V-_2") (pintype "power_in"))
      (node (ref "U1021") (pin "2") (pinfunction "V-_2") (pintype "power_in"))
      (node (ref "U1111") (pin "2") (pinfunction "GND_2") (pintype "passive"))
      (node (ref "U1121") (pin "2") (pinfunction "GND_2") (pintype "passive"))
      (node (ref "U201") (pin "1") (pinfunction "GND_1") (pintype "power_in"))
      (node (ref "U201") (pin "18") (pinfunction "GND_18") (pintype "power_in"))
      (node (ref "U201") (pin "2") (pinfunction "GND_2") (pintype "power_in"))
      (node (ref "U201") (pin "28") (pinfunction "GND_28") (pintype "power_in"))
      (node (ref "U201") (pin "3") (pinfunction "GND_3") (pintype "power_in"))
      (node (ref "U201") (pin "34") (pinfunction "GND_34") (pintype "power_in"))
      (node (ref "U201") (pin "36") (pinfunction "GND_36") (pintype "power_in"))
      (node (ref "U201") (pin "40") (pinfunction "GND_40") (pintype "power_in"))
      (node (ref "U201") (pin "51") (pinfunction "GND_51") (pintype "power_in"))
      (node (ref "U201") (pin "52") (pinfunction "GND_52") (pintype "power_in"))
      (node (ref "U201") (pin "54") (pinfunction "GND_54") (pintype "power_in"))
      (node (ref "U201") (pin "64") (pinfunction "GND_64") (pintype "power_in"))
      (node (ref "U201") (pin "65") (pinfunction "GND_65") (pintype "power_in"))
      (node (ref "U201") (pin "67") (pinfunction "GND_67") (pintype "power_in"))
      (node (ref "U201") (pin "68") (pinfunction "GND_68") (pintype "power_in"))
      (node (ref "U301") (pin "11") (pinfunction "FSYNC_11") (pintype "passive"))
      (node (ref "U301") (pin "18") (pinfunction "GND_18") (pintype "passive"))
      (node (ref "U301") (pin "20") (pinfunction "GND_20") (pintype "passive"))
      (node (ref "U301") (pin "9") (pinfunction "AD0/SDO_9") (pintype "bidirectional"))
      (node (ref "U401") (pin "3") (pinfunction "GND_3") (pintype "passive"))
      (node (ref "U501") (pin "2") (pinfunction "ADDR_2") (pintype "input"))
      (node (ref "U501") (pin "6") (pinfunction "~{RESET}_6") (pintype "passive"))
      (node (ref "U501") (pin "7") (pinfunction "R_7") (pintype "passive"))
      (node (ref "U501") (pin "8") (pinfunction "VSS_8") (pintype "passive"))
      (node (ref "U501") (pin "9") (pinfunction "PAD_9") (pintype "passive"))
      (node (ref "U601") (pin "17") (pinfunction "GPADC1_17") (pintype "passive"))
      (node (ref "U601") (pin "18") (pinfunction "GPADC2_18") (pintype "passive"))
      (node (ref "U601") (pin "2") (pinfunction "GND_2") (pintype "power_in"))
      (node (ref "U601") (pin "21") (pinfunction "GND_21") (pintype "power_in"))
      (node (ref "X111") (pin "10") (pinfunction "10_10") (pintype "passive"))
      (node (ref "X111") (pin "2") (pinfunction "2_2") (pintype "passive"))
      (node (ref "X121") (pin "2") (pinfunction "2_2") (pintype "passive"))
      (node (ref "X121") (pin "5") (pinfunction "5_5") (pintype "passive"))
      (node (ref "X131") (pin "6") (pinfunction "6_6") (pintype "passive"))
      (node (ref "X181") (pin "1") (pinfunction "1_1") (pintype "passive"))
      (node (ref "X291") (pin "2") (pinfunction "2_2") (pintype "passive"))
      (node (ref "X291") (pin "3") (pinfunction "3_3") (pintype "passive"))
      (node (ref "X291") (pin "4") (pinfunction "4_4") (pintype "passive"))
      (node (ref "X291") (pin "5") (pinfunction "5_5") (pintype "passive"))
      (node (ref "X685") (pin "2") (pinfunction "2_2") (pintype "passive"))
      (node (ref "X685") (pin "3") (pinfunction "2_3") (pintype "passive"))
      (node (ref "X685") (pin "4") (pinfunction "2_4") (pintype "passive"))
      (node (ref "X685") (pin "5") (pinfunction "2_5") (pintype "passive"))
      (node (ref "X701") (pin "GND") (pinfunction "GND_GND") (pintype "passive"))
      (node (ref "X801") (pin "G1") (pinfunction "SHIELD_G1") (pintype "passive"))
      (node (ref "X801") (pin "G2") (pinfunction "SHIELD_G2") (pintype "passive"))
      (node (ref "X801") (pin "G3") (pinfunction "SHIELD_G3") (pintype "passive"))
      (node (ref "X801") (pin "G4") (pinfunction "SHIELD_G4") (pintype "passive"))
      (node (ref "X801") (pin "G5") (pinfunction "SHIELD_G5") (pintype "passive"))
      (node (ref "X801") (pin "G6") (pinfunction "SHIELD_G6") (pintype "passive"))
      (node (ref "X801") (pin "G7") (pinfunction "SHIELD_G7") (pintype "passive"))
      (node (ref "X801") (pin "G8") (pinfunction "SHIELD_G8") (pintype "passive"))
      (node (ref "X801") (pin "S5") (pinfunction "S5_S5") (pintype "passive"))
      (node (ref "X801") (pin "T6") (pinfunction "T6_T6") (pintype "passive"))
      (node (ref "X901") (pin "3") (pinfunction "3_3") (pintype "passive"))
    )
    (net (code "28") (name "GPS_1PPS") (class "Default")
      (node (ref "R251") (pin "1") (pinfunction "1_1") (pintype "passive"))
      (node (ref "U101") (pin "58") (pinfunction "PR0_58") (pintype "bidirectional"))
    )
    (net (code "29") (name "GPS_1PPS_DRV") (class "Default")
      (node (ref "R251") (pin "2") (pinfunction "2_2") (pintype "passive"))
      (node (ref "U201") (pin "37") (pinfunction "1PPS_37") (pintype "output"))
    )
    (net (code "30") (name "GPS_ANT") (class "Default")
      (node (ref "C291") (pin "1") (pinfunction "1_1") (pintype "passive"))
      (node (ref "L291") (pin "2") (pinfunction "2_2") (pintype "passive"))
      (node (ref "R291") (pin "1") (pinfunction "1_1") (pintype "passive"))
      (node (ref "X291") (pin "1") (pinfunction "1_1") (pintype "passive"))
    )
    (net (code "31") (name "GPS_PWR") (class "Default")
      (node (ref "L291") (pin "1") (pinfunction "1_1") (pintype "passive"))
      (node (ref "RPOLY291") (pin "1") (pinfunction "1_1") (pintype "passive"))
    )
    (net (code "32") (name "GPS_RF_IN") (class "Default")
      (node (ref "C292") (pin "1") (pinfunction "1_1") (pintype "passive"))
      (node (ref "R291") (pin "2") (pinfunction "2_2") (pintype "passive"))
      (node (ref "U201") (pin "35") (pinfunction "GPS_RF_IN_35") (pintype "input"))
    )
    (net (code "33") (name "GSM_ANT") (class "Default")
      (node (ref "C272") (pin "1") (pinfunction "1_1") (pintype "passive"))
      (node (ref "R271") (pin "2") (pinfunction "2_2") (pintype "passive"))
    )
    (net (code "34") (name "GSM_CTS") (class "Default")
      (node (ref "R223") (pin "2") (pinfunction "2_2") (pintype "passive"))
      (node (ref "U201") (pin "12") (pinfunction "CTS_12") (pintype "output"))
    )
    (net (code "35") (name "GSM_DCD") (class "Default")
      (node (ref "R222") (pin "2") (pinfunction "2_2") (pintype "passive"))
      (node (ref "U201") (pin "11") (pinfunction "DCD_11") (pintype "output"))
    )
    (net (code "36") (name "GSM_DTR") (class "Default")
      (node (ref "R171") (pin "2") (pinfunction "2_2") (pintype "passive"))
      (node (ref "U201") (pin "9") (pinfunction "DTR_9") (pintype "input"))
    )
    (net (code "37") (name "GSM_NETLIGHT") (class "Default")
      (node (ref "R231") (pin "2") (pinfunction "2_2") (pintype "passive"))
      (node (ref "U101") (pin "5") (pinfunction "PA7_5") (pintype "bidirectional"))
    )
    (net (code "38") (name "GSM_NETLIGHT_DRV") (class "Default")
      (node (ref "R231") (pin "1") (pinfunction "1_1") (pintype "passive"))
      (node (ref "U201") (pin "50") (pinfunction "NETLIGHT_50") (pintype "output"))
    )
    (net (code "39") (name "GSM_PCM_CLK") (class "Default")
      (node (ref "R141") (pin "2") (pinfunction "2_2") (pintype "passive"))
      (node (ref "U201") (pin "46") (pinfunction "PCM_CLK_46") (pintype "input"))
    )
    (net (code "40") (name "GSM_PCM_CLK_DRV") (class "Default")
      (node (ref "R141") (pin "1") (pinfunction "1_1") (pintype "passive"))
      (node (ref "U101") (pin "27") (pinfunction "PD1_27") (pintype "bidirectional"))
    )
    (net (code "41") (name "GSM_PCM_IN") (class "Default")
      (node (ref "R142") (pin "2") (pinfunction "2_2") (pintype "passive"))
      (node (ref "U201") (pin "47") (pinfunction "PCM_IN_47") (pintype "input"))
    )
    (net (code "42") (name "GSM_PCM_IN_DRV") (class "Default")
      (node (ref "R142") (pin "1") (pinfunction "1_1") (pintype "passive"))
      (node (ref "U101") (pin "29") (pinfunction "PD3_29") (pintype "bidirectional"))
    )
    (net (code "43") (name "GSM_PCM_OUT") (class "Default")
      (node (ref "R233") (pin "2") (pinfunction "2_2") (pintype "passive"))
      (node (ref "U101") (pin "28") (pinfunction "PD2_28") (pintype "bidirectional"))
    )
    (net (code "44") (name "GSM_PCM_OUT_DRV") (class "Default")
      (node (ref "R233") (pin "1") (pinfunction "1_1") (pintype "passive"))
      (node (ref "U201") (pin "48") (pinfunction "PCM_OUT_48") (pintype "output"))
    )
    (net (code "45") (name "GSM_PCM_SYNC") (class "Default")
      (node (ref "R234") (pin "2") (pinfunction "2_2") (pintype "passive"))
      (node (ref "U101") (pin "26") (pinfunction "PD0_26") (pintype "bidirectional"))
    )
    (net (code "46") (name "GSM_PCM_SYNC_DRV") (class "Default")
      (node (ref "R234") (pin "1") (pinfunction "1_1") (pintype "passive"))
      (node (ref "U201") (pin "45") (pinfunction "PCM_SYNC_45") (pintype "output"))
    )
    (net (code "47") (name "GSM_PWRKEY") (class "Default")
      (node (ref "R162") (pin "2") (pinfunction "2_2") (pintype "passive"))
      (node (ref "U201") (pin "8") (pinfunction "PWRKEY_8") (pintype "input"))
    )
    (net (code "48") (name "GSM_RESET") (class "Default")
      (node (ref "R163") (pin "2") (pinfunction "2_2") (pintype "passive"))
      (node (ref "U201") (pin "16") (pinfunction "RESET_16") (pintype "input"))
    )
    (net (code "49") (name "GSM_RF") (class "Default")
      (node (ref "C271") (pin "1") (pinfunction "1_1") (pintype "passive"))
      (node (ref "R271") (pin "1") (pinfunction "1_1") (pintype "passive"))
      (node (ref "U201") (pin "66") (pinfunction "GSM_RF_IN_66") (pintype "bidirectional"))
    )
    (net (code "50") (name "GSM_RF_SYNC") (class "Default")
      (node (ref "C141") (pin "1") (pinfunction "1_1") (pintype "passive"))
      (node (ref "R241") (pin "2") (pinfunction "2_2") (pintype "passive"))
      (node (ref "U101") (pin "4") (pinfunction "PA6_4") (pintype "bidirectional"))
    )
    (net (code "51") (name "GSM_RF_SYNC_DRV") (class "Default")
      (node (ref "R241") (pin "1") (pinfunction "1_1") (pintype "passive"))
      (node (ref "U201") (pin "63") (pinfunction "RF_SYNC_63") (pintype "output"))
    )
    (net (code "52") (name "GSM_RI") (class "Default")
      (node (ref "R221") (pin "2") (pinfunction "2_2") (pintype "passive"))
      (node (ref "U201") (pin "10") (pinfunction "RI_10") (pintype "output"))
    )
    (net (code "53") (name "GSM_RTS") (class "Default")
      (node (ref "R173") (pin "2") (pinfunction "2_2") (pintype "passive"))
      (node (ref "U201") (pin "13") (pinfunction "RTS_13") (pintype "input"))
    )
    (net (code "54") (name "GSM_RXD") (class "Default")
      (node (ref "R172") (pin "2") (pinfunction "2_2") (pintype "passive"))
      (node (ref "U201") (pin "15") (pinfunction "RXD_15") (pintype "input"))
    )
    (net (code "55") (name "GSM_STATUS") (class "Default")
      (node (ref "R232") (pin "2") (pinfunction "2_2") (pintype "passive"))
      (node (ref "U101") (pin "38") (pinfunction "PE2_38") (pintype "bidirectional"))
    )
    (net (code "56") (name "GSM_STATUS_DRV") (class "Default")
      (node (ref "R232") (pin "1") (pinfunction "1_1") (pintype "passive"))
      (node (ref "U201") (pin "49") (pinfunction "STATUS_49") (pintype "output"))
    )
    (net (code "57") (name "GSM_TXD") (class "Default")
      (node (ref "R224") (pin "2") (pinfunction "2_2") (pintype "passive"))
      (node (ref "U201") (pin "14") (pinfunction "TXD_14") (pintype "output"))
    )
    (net (code "58") (name "GSM_VDD_EXT") (class "Default")
      (node (ref "R161") (pin "2") (pinfunction "2_2") (pintype "passive"))
      (node (ref "U201") (pin "7") (pinfunction "VDD_EXT(2.8VOUT)_7") (pintype "output"))
    )
    (net (code "59") (name "I2C2_INT") (class "Default")
      (node (ref "R301") (pin "2") (pinfunction "2_2") (pintype "passive"))
      (node (ref "U101") (pin "6") (pinfunction "PB0_6") (pintype "bidirectional"))
    )
    (net (code "60") (name "IO_ADC4") (class "Default")
      (node (ref "U101") (pin "2") (pinfunction "PA4_2") (pintype "bidirectional"))
      (node (ref "X181") (pin "3") (pinfunction "3_3") (pintype "passive"))
    )
    (net (code "61") (name "IO_ADC5") (class "Default")
      (node (ref "U101") (pin "3") (pinfunction "PA5_3") (pintype "bidirectional"))
      (node (ref "X181") (pin "5") (pinfunction "5_5") (pintype "passive"))
    )
    (net (code "62") (name "IO_DAC0") (class "Default")
      (node (ref "U101") (pin "8") (pinfunction "PB2_8") (pintype "bidirectional"))
      (node (ref "X181") (pin "4") (pinfunction "4_4") (pintype "passive"))
    )
    (net (code "63") (name "IO_DAC1") (class "Default")
      (node (ref "U101") (pin "9") (pinfunction "PB3_9") (pintype "bidirectional"))
      (node (ref "X181") (pin "6") (pinfunction "6_6") (pintype "passive"))
    )
    (net (code "64") (name "IO_OC1A") (class "Default")
      (node (ref "U101") (pin "30") (pinfunction "PD4_30") (pintype "bidirectional"))
      (node (ref "X181") (pin "2") (pinfunction "2_2") (pintype "passive"))
    )
    (net (code "65") (name "MPU_INT") (class "Default")
      (node (ref "R301") (pin "1") (pinfunction "1_1") (pintype "passive"))
      (node (ref "U301") (pin "12") (pinfunction "INT_12") (pintype "output"))
    )
    (net (code "66") (name "Net-(C611-Pad1)") (class "Default")
      (node (ref "C611") (pin "1") (pinfunction "1_1") (pintype "passive"))
      (node (ref "U601") (pin "1") (pinfunction "VDD_ANA_1") (pintype "passive"))
    )
    (net (code "67") (name "Net-(C612-Pad1)") (class "Default")
      (node (ref "C612") (pin "1") (pinfunction "1_1") (pintype "passive"))
      (node (ref "U601") (pin "5") (pinfunction "VDD_ANA_5") (pintype "passive"))
    )
    (net (code "68") (name "Net-(C701-Pad1)") (class "Default")
      (node (ref "C701") (pin "1") (pinfunction "1_1") (pintype "passive"))
      (node (ref "R701") (pin "1") (pinfunction "1_1") (pintype "passive"))
      (node (ref "X701") (pin "JSHIELD") (pinfunction "SHIELD_JSHIELD") (pintype "passive"))
      (node (ref "X701") (pin "JSHIELD@2") (pinfunction "SHIELD_JSHIELD@2") (pintype "passive"))
      (node (ref "X701") (pin "JSHIELD@3") (pinfunction "SHIELD_JSHIELD@3") (pintype "passive"))
      (node (ref "X701") (pin "JSHIELD@4") (pinfunction "SHIELD_JSHIELD@4") (pintype "passive"))
      (node (ref "X701") (pin "JSHIELD@5") (pinfunction "SHIELD_JSHIELD@5") (pintype "passive"))
      (node (ref "X701") (pin "JSHIELD@6") (pinfunction "SHIELD_JSHIELD@6") (pintype "passive"))
    )
    (net (code "69") (name "Net-(Q651-2)") (class "Default")
      (node (ref "Q651") (pin "3") (pinfunction "2_3") (pintype "passive"))
      (node (ref "U601") (pin "19") (pinfunction "CLK16N_19") (pintype "passive"))
    )
    (net (code "70") (name "Net-(RPOLY901-Pad1)") (class "Default")
      (node (ref "RPOLY901") (pin "1") (pinfunction "1_1") (pintype "passive"))
      (node (ref "X901") (pin "1") (pinfunction "1_1") (pintype "passive"))
    )
    (net (code "71") (name "Net-(U101A-TOSC1)") (class "Default")
      (node (ref "Q101") (pin "2") (pinfunction "2_2") (pintype "passive"))
      (node (ref "U101") (pin "43") (pinfunction "TOSC1_43") (pintype "passive"))
    )
    (net (code "72") (name "Net-(U101A-TOSC2)") (class "Default")
      (node (ref "Q101") (pin "1") (pinfunction "1_1") (pintype "passive"))
      (node (ref "U101") (pin "42") (pinfunction "TOSC2_42") (pintype "passive"))
    )
    (net (code "73") (name "Net-(U301-REGOUT)") (class "Default")
      (node (ref "C302") (pin "1") (pinfunction "1_1") (pintype "passive"))
      (node (ref "U301") (pin "10") (pinfunction "REGOUT_10") (pintype "passive"))
    )
    (net (code "74") (name "Net-(U601-CLK16P)") (class "Default")
      (node (ref "Q651") (pin "1") (pinfunction "1_1") (pintype "passive"))
      (node (ref "U601") (pin "20") (pinfunction "CLK16P_20") (pintype "passive"))
    )
    (net (code "75") (name "Net-(U1021--IN)") (class "Default")
      (node (ref "R1021") (pin "1") (pinfunction "1_1") (pintype "passive"))
      (node (ref "U1021") (pin "4") (pinfunction "-IN_4") (pintype "input"))
    )
    (net (code "76") (name "Net-(U1111-VIN)") (class "Default")
      (node (ref "C1111") (pin "1") (pinfunction "1_1") (pintype "passive"))
      (node (ref "C1121") (pin "1") (pinfunction "1_1") (pintype "passive"))
      (node (ref "D1121") (pin "C") (pinfunction "C_C") (pintype "passive"))
      (node (ref "D1122") (pin "C") (pinfunction "C_C") (pintype "passive"))
      (node (ref "R1113") (pin "1") (pinfunction "1_1") (pintype "passive"))
      (node (ref "U1111") (pin "5") (pinfunction "VIN_5") (pintype "power_in"))
      (node (ref "U1121") (pin "3") (pinfunction "EN_3") (pintype "input"))
      (node (ref "U1121") (pin "4") (pinfunction "VIN_4") (pintype "power_in"))
    )
    (net (code "77") (name "Net-(X701-J_D+)") (class "Default")
      (node (ref "R723") (pin "1") (pinfunction "1_1") (pintype "passive"))
      (node (ref "R724") (pin "1") (pinfunction "1_1") (pintype "passive"))
      (node (ref "X701") (pin "D+") (pinfunction "J_D+_D+") (pintype "bidirectional"))
    )
    (net (code "78") (name "Net-(X701-J_D-)") (class "Default")
      (node (ref "R721") (pin "1") (pinfunction "1_1") (pintype "passive"))
      (node (ref "R722") (pin "1") (pinfunction "1_1") (pintype "passive"))
      (node (ref "X701") (pin "D-") (pinfunction "J_D-_D-") (pintype "bidirectional"))
    )
    (net (code "79") (name "Net-(X701-J_ID)") (class "Default")
      (node (ref "R725") (pin "1") (pinfunction "1_1") (pintype "passive"))
      (node (ref "X701") (pin "ID") (pinfunction "J_ID_ID") (pintype "bidirectional"))
    )
    (net (code "80") (name "Net-(X701-J_VUSB)") (class "Default")
      (node (ref "RPOLY711") (pin "1") (pinfunction "1_1") (pintype "passive"))
      (node (ref "X701") (pin "VBUS") (pinfunction "J_VUSB_VBUS") (pintype "power_in"))
    )
    (net (code "81") (name "PDI_CLK") (class "Default")
      (node (ref "R112") (pin "1") (pinfunction "1_1") (pintype "passive"))
      (node (ref "R132") (pin "1") (pinfunction "1_1") (pintype "passive"))
      (node (ref "X111") (pin "6") (pinfunction "6_6") (pintype "passive"))
      (node (ref "X131") (pin "5") (pinfunction "5_5") (pintype "passive"))
    )
    (net (code "82") (name "PDI_CLK_CPU") (class "Default")
      (node (ref "R132") (pin "2") (pinfunction "2_2") (pintype "passive"))
      (node (ref "U101") (pin "57") (pinfunction "~{RESET}/PDI_CLK_57") (pintype "input"))
    )
    (net (code "83") (name "PDI_DATA") (class "Default")
      (node (ref "R131") (pin "1") (pinfunction "1_1") (pintype "passive"))
      (node (ref "X131") (pin "1") (pinfunction "1_1") (pintype "passive"))
    )
    (net (code "84") (name "PDI_DATA_CPU") (class "Default")
      (node (ref "R131") (pin "2") (pinfunction "2_2") (pintype "passive"))
      (node (ref "U101") (pin "56") (pinfunction "PDI_DATA_56") (pintype "input"))
    )
    (net (code "85") (name "POWERED_GSM") (class "Default")
      (node (ref "R161") (pin "1") (pinfunction "1_1") (pintype "passive"))
      (node (ref "U101") (pin "39") (pinfunction "PE3_39") (pintype "bidirectional"))
    )
    (net (code "86") (name "PWRKEY_GSM") (class "Default")
      (node (ref "R162") (pin "1") (pinfunction "1_1") (pintype "passive"))
      (node (ref "U101") (pin "40") (pinfunction "PE4_40") (pintype "bidirectional"))
    )
    (net (code "87") (name "RESET_GSM") (class "Default")
      (node (ref "R163") (pin "1") (pinfunction "1_1") (pintype "passive"))
      (node (ref "U101") (pin "41") (pinfunction "PE5_41") (pintype "bidirectional"))
    )
    (net (code "88") (name "RI1") (class "Default")
      (node (ref "R221") (pin "1") (pinfunction "1_1") (pintype "passive"))
      (node (ref "U101") (pin "50") (pinfunction "PF4_50") (pintype "bidirectional"))
    )
    (net (code "89") (name "RTS1") (class "Default")
      (node (ref "R223") (pin "1") (pinfunction "1_1") (pintype "passive"))
      (node (ref "U101") (pin "54") (pinfunction "PF6_54") (pintype "bidirectional"))
    )
    (net (code "90") (name "RXD1") (class "Default")
      (node (ref "R224") (pin "1") (pinfunction "1_1") (pintype "passive"))
      (node (ref "U101") (pin "48") (pinfunction "PF2_48") (pintype "bidirectional"))
    )
    (net (code "91") (name "SCL1") (class "Default")
      (node (ref "R212") (pin "2") (pinfunction "2_2") (pintype "passive"))
      (node (ref "R401") (pin "1") (pinfunction "1_1") (pintype "passive"))
      (node (ref "U101") (pin "37") (pinfunction "PE1_37") (pintype "bidirectional"))
      (node (ref "U201") (pin "39") (pinfunction "SCL_39") (pintype "bidirectional"))
      (node (ref "U301") (pin "23") (pinfunction "SCL/SCLK_23") (pintype "input"))
      (node (ref "U401") (pin "8") (pinfunction "SCL_SCLK_8") (pintype "input"))
      (node (ref "U501") (pin "4") (pinfunction "SCL_4") (pintype "input"))
    )
    (net (code "92") (name "SCL2") (class "Default")
      (node (ref "U101") (pin "17") (pinfunction "PC1_17") (pintype "bidirectional"))
      (node (ref "X121") (pin "1") (pinfunction "1_1") (pintype "passive"))
    )
    (net (code "93") (name "SDA1") (class "Default")
      (node (ref "R211") (pin "2") (pinfunction "2_2") (pintype "passive"))
      (node (ref "R402") (pin "1") (pinfunction "1_1") (pintype "passive"))
      (node (ref "U101") (pin "36") (pinfunction "PE0_36") (pintype "bidirectional"))
      (node (ref "U201") (pin "38") (pinfunction "SDA_38") (pintype "bidirectional"))
      (node (ref "U301") (pin "24") (pinfunction "SDA/SDI_24") (pintype "bidirectional"))
      (node (ref "U401") (pin "7") (pinfunction "SDI_SDA_7") (pintype "bidirectional"))
      (node (ref "U501") (pin "1") (pinfunction "SDA_1") (pintype "bidirectional"))
    )
    (net (code "94") (name "SDA2") (class "Default")
      (node (ref "U101") (pin "16") (pinfunction "PC0_16") (pintype "bidirectional"))
      (node (ref "X121") (pin "3") (pinfunction "3_3") (pintype "passive"))
    )
    (net (code "95") (name "SIM_CLK") (class "Default")
      (node (ref "U201") (pin "31") (pinfunction "SIM_CLK_31") (pintype "output"))
      (node (ref "X801") (pin "S3") (pinfunction "S3_S3") (pintype "input"))
    )
    (net (code "96") (name "SIM_IO") (class "Default")
      (node (ref "U201") (pin "30") (pinfunction "SIM_DATA_30") (pintype "bidirectional"))
      (node (ref "X801") (pin "S7") (pinfunction "S7_S7") (pintype "bidirectional"))
    )
    (net (code "97") (name "SIM_RST") (class "Default")
      (node (ref "U201") (pin "32") (pinfunction "SIM_RST_32") (pintype "output"))
      (node (ref "X801") (pin "S2") (pinfunction "S2_S2") (pintype "bidirectional"))
    )
    (net (code "98") (name "SIM_VBUS") (class "Default")
      (node (ref "JP201") (pin "2") (pinfunction "2_2") (pintype "passive"))
      (node (ref "U201") (pin "25") (pinfunction "VBUS_25") (pintype "power_in"))
    )
    (net (code "99") (name "SIM_VCC") (class "Default")
      (node (ref "U201") (pin "29") (pinfunction "SIM_VDD_29") (pintype "power_in"))
      (node (ref "X801") (pin "S1") (pinfunction "S1_S1") (pintype "power_in"))
    )
    (net (code "100") (name "SIM_VPP") (class "Default")
      (node (ref "U201") (pin "33") (pinfunction "SIM_PRE_33") (pintype "input"))
      (node (ref "X801") (pin "S6") (pinfunction "S6_S6") (pintype "power_in"))
    )
    (net (code "101") (name "SW") (class "Default")
      (node (ref "D1111") (pin "C") (pinfunction "C_C") (pintype "passive"))
      (node (ref "L1111") (pin "2") (pinfunction "2_2") (pintype "passive"))
      (node (ref "U1111") (pin "1") (pinfunction "SW_1") (pintype "output"))
    )
    (net (code "102") (name "T4") (class "Default")
      (node (ref "X801") (pin "T4") (pinfunction "T4_T4") (pintype "power_in"))
    )
    (net (code "103") (name "TCK") (class "Default")
      (node (ref "U101") (pin "12") (pinfunction "PB6_12") (pintype "bidirectional"))
      (node (ref "X111") (pin "1") (pinfunction "1_1") (pintype "passive"))
    )
    (net (code "104") (name "TCXO_20MHZ") (class "Default")
      (node (ref "R1013") (pin "2") (pinfunction "2_2") (pintype "passive"))
      (node (ref "U101") (pin "59") (pinfunction "PR1_59") (pintype "bidirectional"))
    )
    (net (code "105") (name "TDI") (class "Default")
      (node (ref "U101") (pin "11") (pinfunction "PB5_11") (pintype "bidirectional"))
      (node (ref "X111") (pin "9") (pinfunction "9_9") (pintype "passive"))
    )
    (net (code "106") (name "TDO") (class "Default")
      (node (ref "U101") (pin "13") (pinfunction "PB7_13") (pintype "bidirectional"))
      (node (ref "X111") (pin "3") (pinfunction "3_3") (pintype "passive"))
    )
    (net (code "107") (name "TMS") (class "Default")
      (node (ref "U101") (pin "10") (pinfunction "PB4_10") (pintype "bidirectional"))
      (node (ref "X111") (pin "5") (pinfunction "5_5") (pintype "passive"))
    )
    (net (code "108") (name "TRSH") (class "Default")
      (node (ref "C1011") (pin "1") (pinfunction "1_1") (pintype "passive"))
      (node (ref "R1011") (pin "2") (pinfunction "2_2") (pintype "passive"))
      (node (ref "R1012") (pin "1") (pinfunction "1_1") (pintype "passive"))
      (node (ref "U1011") (pin "4") (pinfunction "-IN_4") (pintype "input"))
    )
    (net (code "109") (name "TXD1") (class "Default")
      (node (ref "R172") (pin "1") (pinfunction "1_1") (pintype "passive"))
      (node (ref "U101") (pin "49") (pinfunction "PF3_49") (pintype "bidirectional"))
    )
    (net (code "110") (name "USB_D_N") (class "Default")
      (node (ref "D722") (pin "C") (pinfunction "C_C") (pintype "passive"))
      (node (ref "R722") (pin "2") (pinfunction "2_2") (pintype "passive"))
      (node (ref "U101") (pin "32") (pinfunction "PD6_32") (pintype "bidirectional"))
    )
    (net (code "111") (name "USB_D_P") (class "Default")
      (node (ref "D721") (pin "C") (pinfunction "C_C") (pintype "passive"))
      (node (ref "R723") (pin "2") (pinfunction "2_2") (pintype "passive"))
      (node (ref "U101") (pin "33") (pinfunction "PD7_33") (pintype "bidirectional"))
    )
    (net (code "112") (name "USB_ID") (class "Default")
      (node (ref "R725") (pin "2") (pinfunction "2_2") (pintype "passive"))
      (node (ref "U101") (pin "7") (pinfunction "PB1_7") (pintype "bidirectional"))
    )
    (net (code "113") (name "USB_RESET") (class "Default")
      (node (ref "R151") (pin "2") (pinfunction "2_2") (pintype "passive"))
      (node (ref "R721") (pin "2") (pinfunction "2_2") (pintype "passive"))
    )
    (net (code "114") (name "USB_RESET_DRV") (class "Default")
      (node (ref "R151") (pin "1") (pinfunction "1_1") (pintype "passive"))
      (node (ref "U101") (pin "31") (pinfunction "PD5_31") (pintype "bidirectional"))
    )
    (net (code "115") (name "VBAT") (class "Default")
      (node (ref "C201") (pin "1") (pinfunction "1_1") (pintype "passive"))
      (node (ref "C901") (pin "1") (pinfunction "1_1") (pintype "passive"))
      (node (ref "D1122") (pin "A") (pinfunction "A_A") (pintype "passive"))
      (node (ref "D201") (pin "C") (pinfunction "C_C") (pintype "passive"))
      (node (ref "R1132") (pin "1") (pinfunction "1_1") (pintype "passive"))
      (node (ref "RPOLY901") (pin "2") (pinfunction "2_2") (pintype "passive"))
      (node (ref "U201") (pin "4") (pinfunction "VBAT_4") (pintype "power_in"))
      (node (ref "U201") (pin "5") (pinfunction "VBAT_5") (pintype "power_in"))
      (node (ref "U201") (pin "6") (pinfunction "VBAT_6") (pintype "power_in"))
    )
    (net (code "116") (name "VREF") (class "Default")
      (node (ref "R111") (pin "1") (pinfunction "1_1") (pintype "passive"))
      (node (ref "X111") (pin "4") (pinfunction "4_4") (pintype "passive"))
    )
    (net (code "117") (name "XO_AMP") (class "Default")
      (node (ref "R1013") (pin "1") (pinfunction "1_1") (pintype "passive"))
      (node (ref "U1011") (pin "1") (pinfunction "OUT_1") (pintype "output"))
    )
    (net (code "118") (name "XO_DRV") (class "Default")
      (node (ref "U1001") (pin "3") (pinfunction "OUT_3") (pintype "output"))
      (node (ref "U1011") (pin "3") (pinfunction "+IN_3") (pintype "input"))
    )
    (net (code "119") (name "XO_LP") (class "Default")
      (node (ref "C1001") (pin "1") (pinfunction "1_1") (pintype "passive"))
      (node (ref "R1001") (pin "2") (pinfunction "2_2") (pintype "passive"))
      (node (ref "R1002") (pin "1") (pinfunction "1_1") (pintype "passive"))
      (node (ref "U1021") (pin "3") (pinfunction "+IN_3") (pintype "input"))
    )
    (net (code "120") (name "XO_VC") (class "Default")
      (node (ref "R1002") (pin "2") (pinfunction "2_2") (pintype "passive"))
      (node (ref "U1001") (pin "1") (pinfunction "VC_1") (pintype "input"))
    )
    (net (code "121") (name "XO_VC_PWM") (class "Default")
      (node (ref "R1001") (pin "1") (pinfunction "1_1") (pintype "passive"))
      (node (ref "U101") (pin "18") (pinfunction "PC2_18") (pintype "bidirectional"))
    )
    (net (code "122") (name "unconnected-(U201-ADC1-Pad23)") (class "Default")
      (node (ref "U201") (pin "23") (pinfunction "ADC1_23") (pintype "input"))
    )
    (net (code "123") (name "unconnected-(U201-ADC2-Pad24)") (class "Default")
      (node (ref "U201") (pin "24") (pinfunction "ADC2_24") (pintype "input"))
    )
    (net (code "124") (name "unconnected-(U201-COL0-Pad62)") (class "Default")
      (node (ref "U201") (pin "62") (pinfunction "COL0_62") (pintype "input"))
    )
    (net (code "125") (name "unconnected-(U201-COL1-Pad61)") (class "Default")
      (node (ref "U201") (pin "61") (pinfunction "COL1_61") (pintype "input"))
    )
    (net (code "126") (name "unconnected-(U201-COL2-Pad60)") (class "Default")
      (node (ref "U201") (pin "60") (pinfunction "COL2_60") (pintype "input"))
    )
    (net (code "127") (name "unconnected-(U201-COL3-Pad59)") (class "Default")
      (node (ref "U201") (pin "59") (pinfunction "COL3_59") (pintype "input"))
    )
    (net (code "128") (name "unconnected-(U201-GPIO5-Pad43)") (class "Default")
      (node (ref "U201") (pin "43") (pinfunction "GPIO5_43") (pintype "bidirectional"))
    )
    (net (code "129") (name "unconnected-(U201-GPIO6-Pad44)") (class "Default")
      (node (ref "U201") (pin "44") (pinfunction "GPIO6_44") (pintype "bidirectional"))
    )
    (net (code "130") (name "unconnected-(U201-MIC1N-Pad20)") (class "Default")
      (node (ref "U201") (pin "20") (pinfunction "MIC1N_20") (pintype "input"))
    )
    (net (code "131") (name "unconnected-(U201-MIC1P-Pad19)") (class "Default")
      (node (ref "U201") (pin "19") (pinfunction "MIC1P_19") (pintype "input"))
    )
    (net (code "132") (name "unconnected-(U201-PWM1-Pad42)") (class "Default")
      (node (ref "U201") (pin "42") (pinfunction "PWM1_42") (pintype "output"))
    )
    (net (code "133") (name "unconnected-(U201-PWM2-Pad41)") (class "Default")
      (node (ref "U201") (pin "41") (pinfunction "PWM2_41") (pintype "output"))
    )
    (net (code "134") (name "unconnected-(U201-ROW0-Pad58)") (class "Default")
      (node (ref "U201") (pin "58") (pinfunction "ROW0_58") (pintype "output"))
    )
    (net (code "135") (name "unconnected-(U201-ROW1-Pad57)") (class "Default")
      (node (ref "U201") (pin "57") (pinfunction "ROW1_57") (pintype "output"))
    )
    (net (code "136") (name "unconnected-(U201-ROW2-Pad56)") (class "Default")
      (node (ref "U201") (pin "56") (pinfunction "ROW2_56") (pintype "output"))
    )
    (net (code "137") (name "unconnected-(U201-ROW3-Pad55)") (class "Default")
      (node (ref "U201") (pin "55") (pinfunction "ROW3_55") (pintype "output"))
    )
    (net (code "138") (name "unconnected-(U201-SPK1N-Pad22)") (class "Default")
      (node (ref "U201") (pin "22") (pinfunction "SPK1N_22") (pintype "output"))
    )
    (net (code "139") (name "unconnected-(U201-SPK1P-Pad21)") (class "Default")
      (node (ref "U201") (pin "21") (pinfunction "SPK1P_21") (pintype "output"))
    )
    (net (code "140") (name "unconnected-(U201-USB_DM-Pad27)") (class "Default")
      (node (ref "U201") (pin "27") (pinfunction "USB_DM_27") (pintype "bidirectional"))
    )
    (net (code "141") (name "unconnected-(U201-USB_DP-Pad26)") (class "Default")
      (node (ref "U201") (pin "26") (pinfunction "USB_DP_26") (pintype "bidirectional"))
    )
    (net (code "142") (name "unconnected-(U301-AUX_CL-Pad7)") (class "Default")
      (node (ref "U301") (pin "7") (pinfunction "AUX_CL_7") (pintype "output"))
    )
    (net (code "143") (name "unconnected-(U301-AUX_DA-Pad21)") (class "Default")
      (node (ref "U301") (pin "21") (pinfunction "AUX_DA_21") (pintype "bidirectional"))
    )
    (net (code "144") (name "unconnected-(U401-NC-Pad5)") (class "Default")
      (node (ref "U401") (pin "5") (pinfunction "NC_5") (pintype "no_connect"))
    )
    (net (code "145") (name "unconnected-(U401-SDO-Pad6)") (class "Default")
      (node (ref "U401") (pin "6") (pinfunction "SDO_6") (pintype "output"))
    )
    (net (code "146") (name "unconnected-(U501-ALERT-Pad3)") (class "Default")
      (node (ref "U501") (pin "3") (pinfunction "ALERT_3") (pintype "output"))
    )
    (net (code "147") (name "unconnected-(U601-FILT-Pad6)") (class "Default")
      (node (ref "U601") (pin "6") (pinfunction "FILT_6") (pintype "passive"))
    )
    (net (code "148") (name "unconnected-(U601-SYSCLK-Pad9)") (class "Default")
      (node (ref "U601") (pin "9") (pinfunction "SYSCLK_9") (pintype "bidirectional"))
    )
    (net (code "149") (name "unconnected-(U601-TCXO_EN-Pad15)") (class "Default")
      (node (ref "U601") (pin "15") (pinfunction "TCXO_EN_15") (pintype "bidirectional"))
    )
    (net (code "150") (name "unconnected-(U1121-REF-Pad1)") (class "Default")
      (node (ref "U1121") (pin "1") (pinfunction "REF_1") (pintype "no_connect"))
    )
    (net (code "151") (name "unconnected-(X111-Pad8)") (class "Default")
      (node (ref "X111") (pin "8") (pinfunction "8_8") (pintype "passive"))
    )
    (net (code "152") (name "unconnected-(X131-Pad3)") (class "Default")
      (node (ref "X131") (pin "3") (pinfunction "3_3") (pintype "passive"))
    )
    (net (code "153") (name "unconnected-(X131-Pad4)") (class "Default")
      (node (ref "X131") (pin "4") (pinfunction "4_4") (pintype "passive"))
    )
    (net (code "154") (name "unconnected-(X801-PadS4)") (class "Default")
      (node (ref "X801") (pin "S4") (pinfunction "S4_S4") (pintype "passive"))
    )
    (net (code "155") (name "unconnected-(X801-PadS8)") (class "Default")
      (node (ref "X801") (pin "S8") (pinfunction "S8_S8") (pintype "passive"))
    )
    (net (code "156") (name "unconnected-(X801-PadSW)") (class "Default")
      (node (ref "X801") (pin "SW") (pinfunction "SW_SW") (pintype "passive"))
    )
    (net (code "157") (name "unconnected-(X801-PadT1)") (class "Default")
      (node (ref "X801") (pin "T1") (pinfunction "T1_T1") (pintype "bidirectional"))
    )
    (net (code "158") (name "unconnected-(X801-PadT2)") (class "Default")
      (node (ref "X801") (pin "T2") (pinfunction "T2_T2") (pintype "bidirectional"))
    )
    (net (code "159") (name "unconnected-(X801-PadT3)") (class "Default")
      (node (ref "X801") (pin "T3") (pinfunction "T3_T3") (pintype "bidirectional"))
    )
    (net (code "160") (name "unconnected-(X801-PadT5)") (class "Default")
      (node (ref "X801") (pin "T5") (pinfunction "T5_T5") (pintype "input"))
    )
    (net (code "161") (name "unconnected-(X801-PadT7)") (class "Default")
      (node (ref "X801") (pin "T7") (pinfunction "T7_T7") (pintype "bidirectional"))
    )
    (net (code "162") (name "unconnected-(X801-PadT8)") (class "Default")
      (node (ref "X801") (pin "T8") (pinfunction "T8_T8") (pintype "bidirectional"))
    )
    (net (code "163") (name "unconnected-(X901-Pad2)") (class "Default")
      (node (ref "X901") (pin "2") (pinfunction "2_2") (pintype "passive"))
    )
  )
)
